# e-ink-display-v010.net
KiCad netlist of a schematic drawn in EAGLE
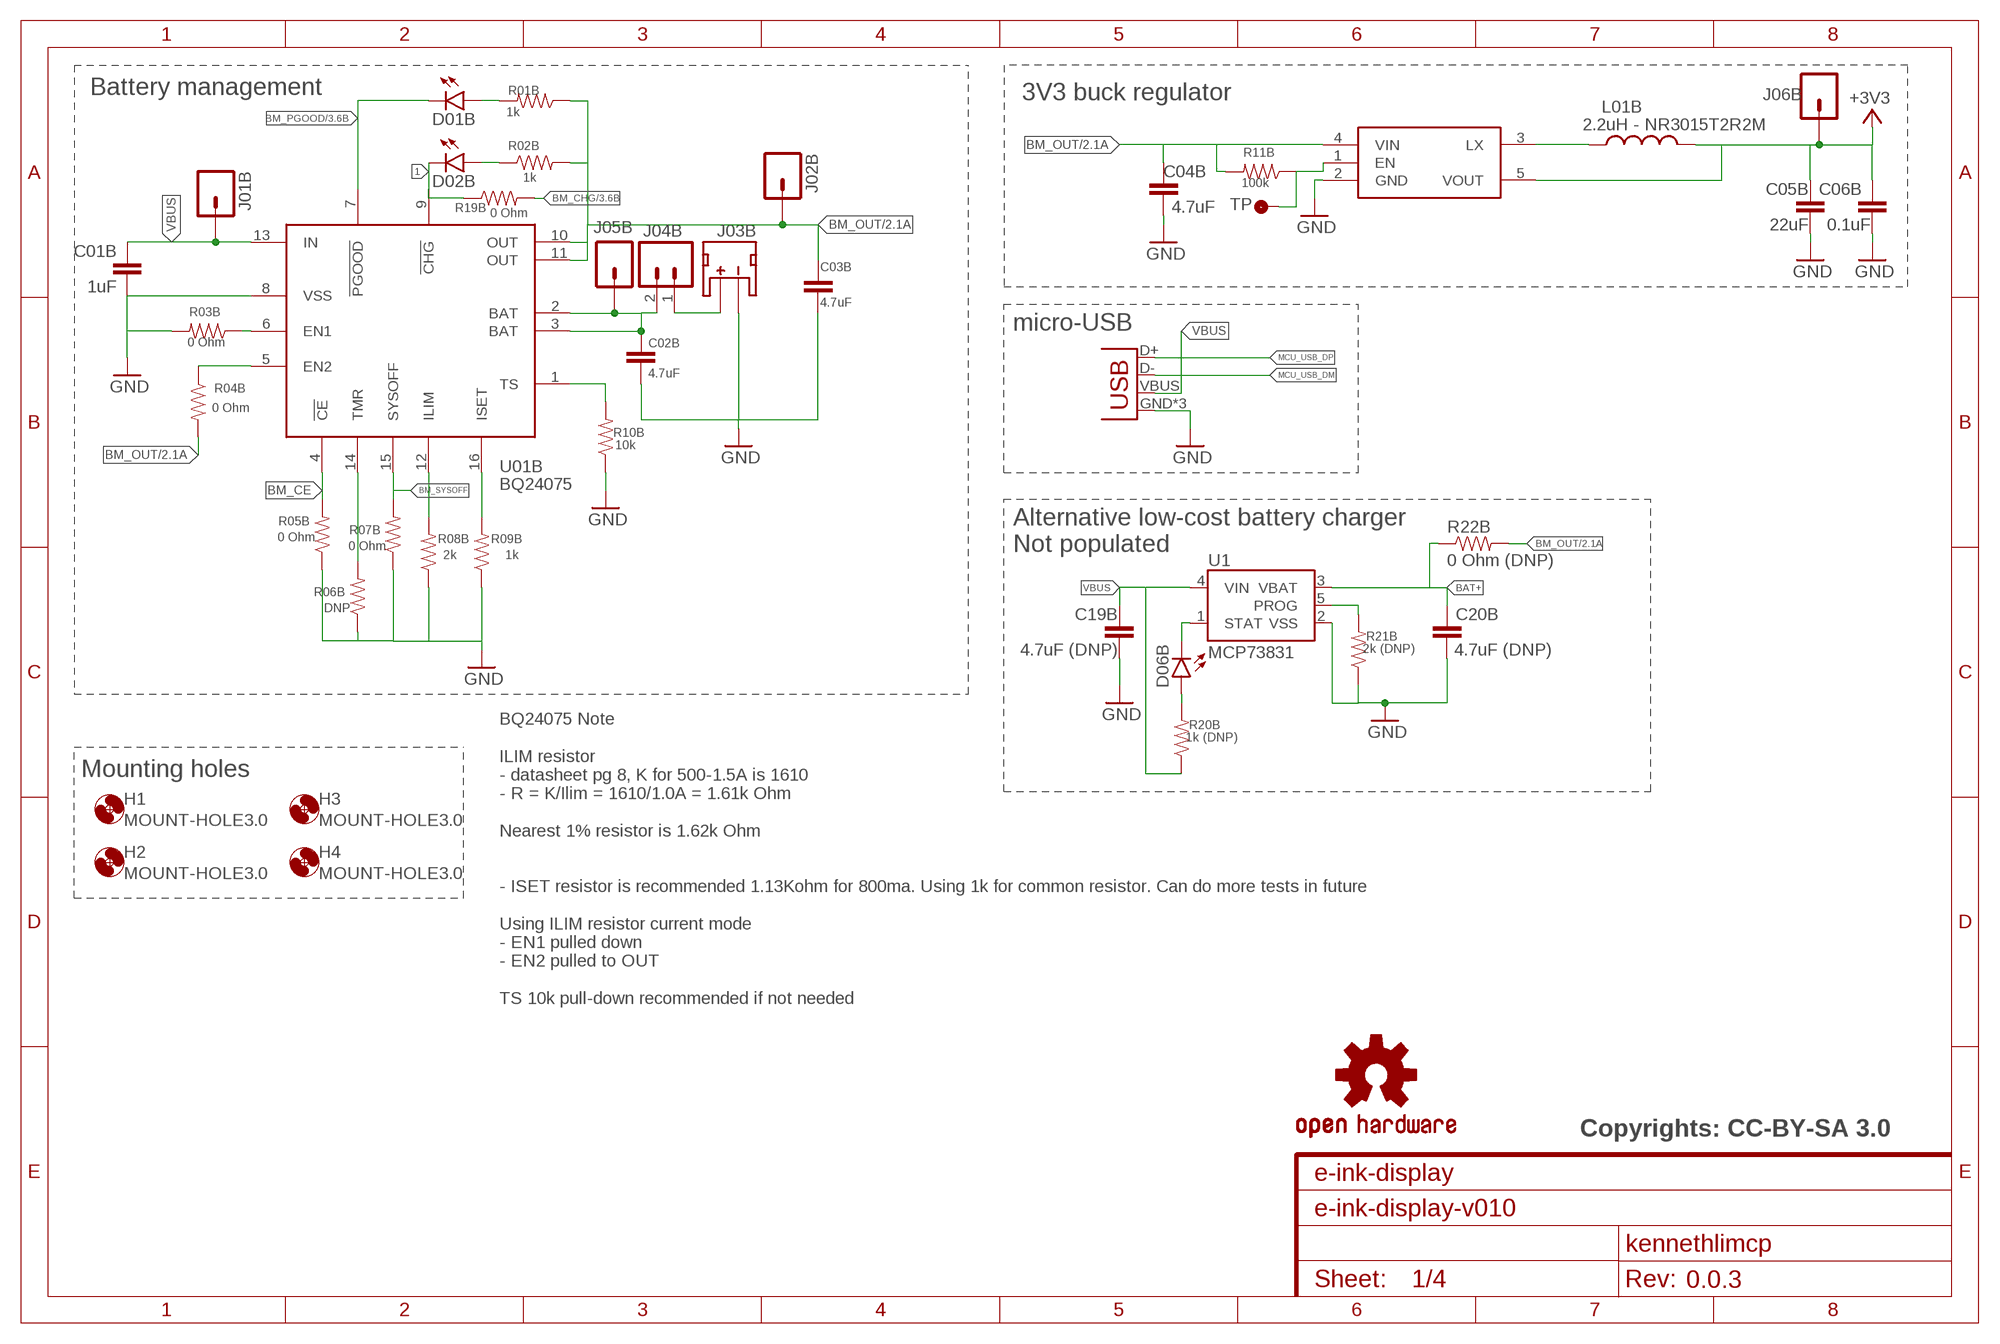
[diagram p0: schematic, sheet 1]
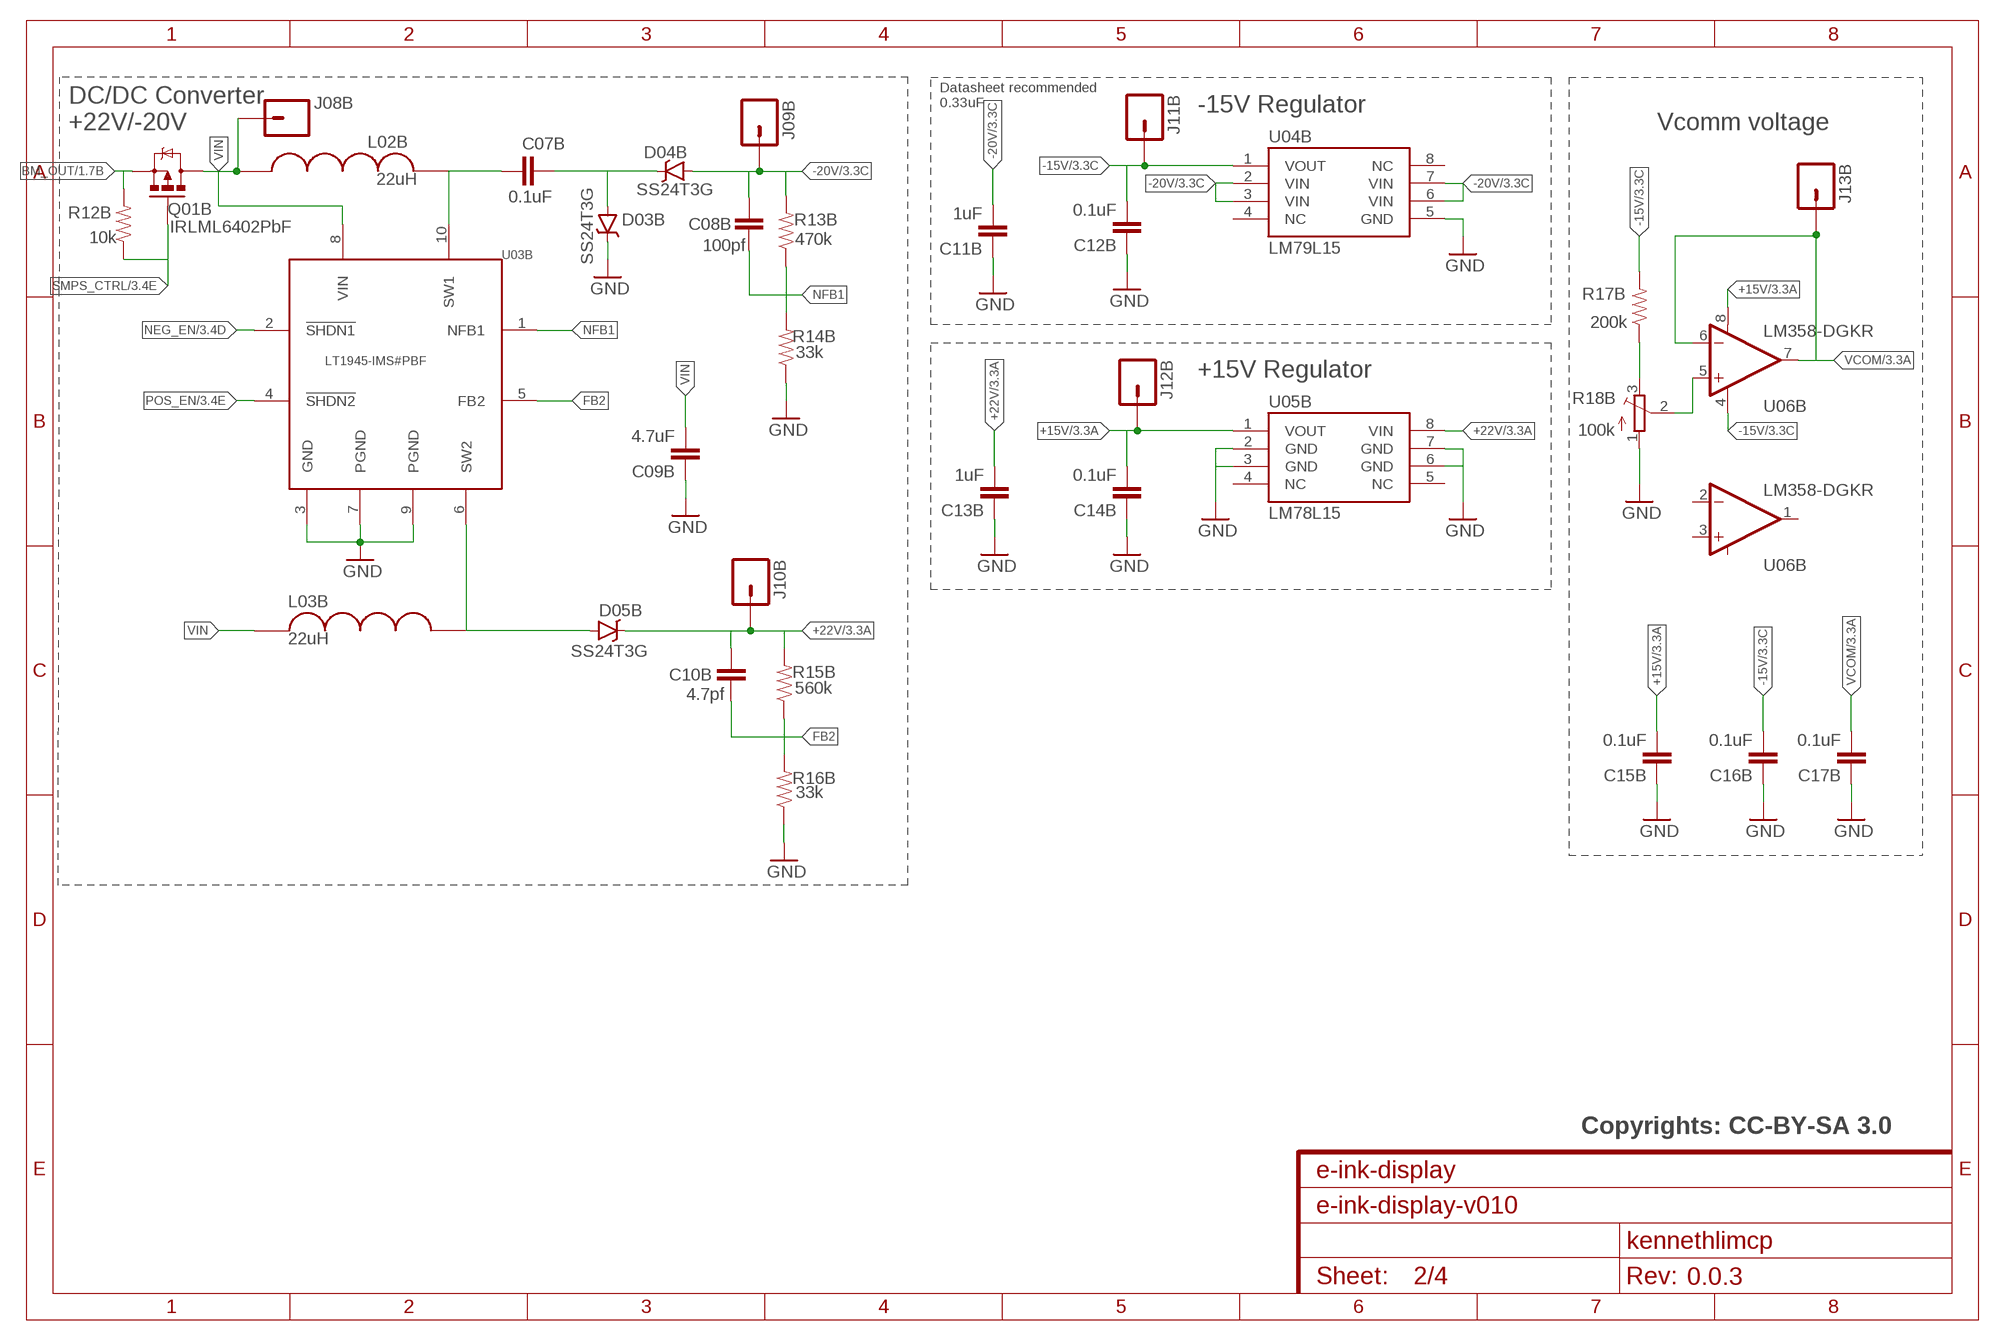
[diagram p1: schematic, sheet 2]
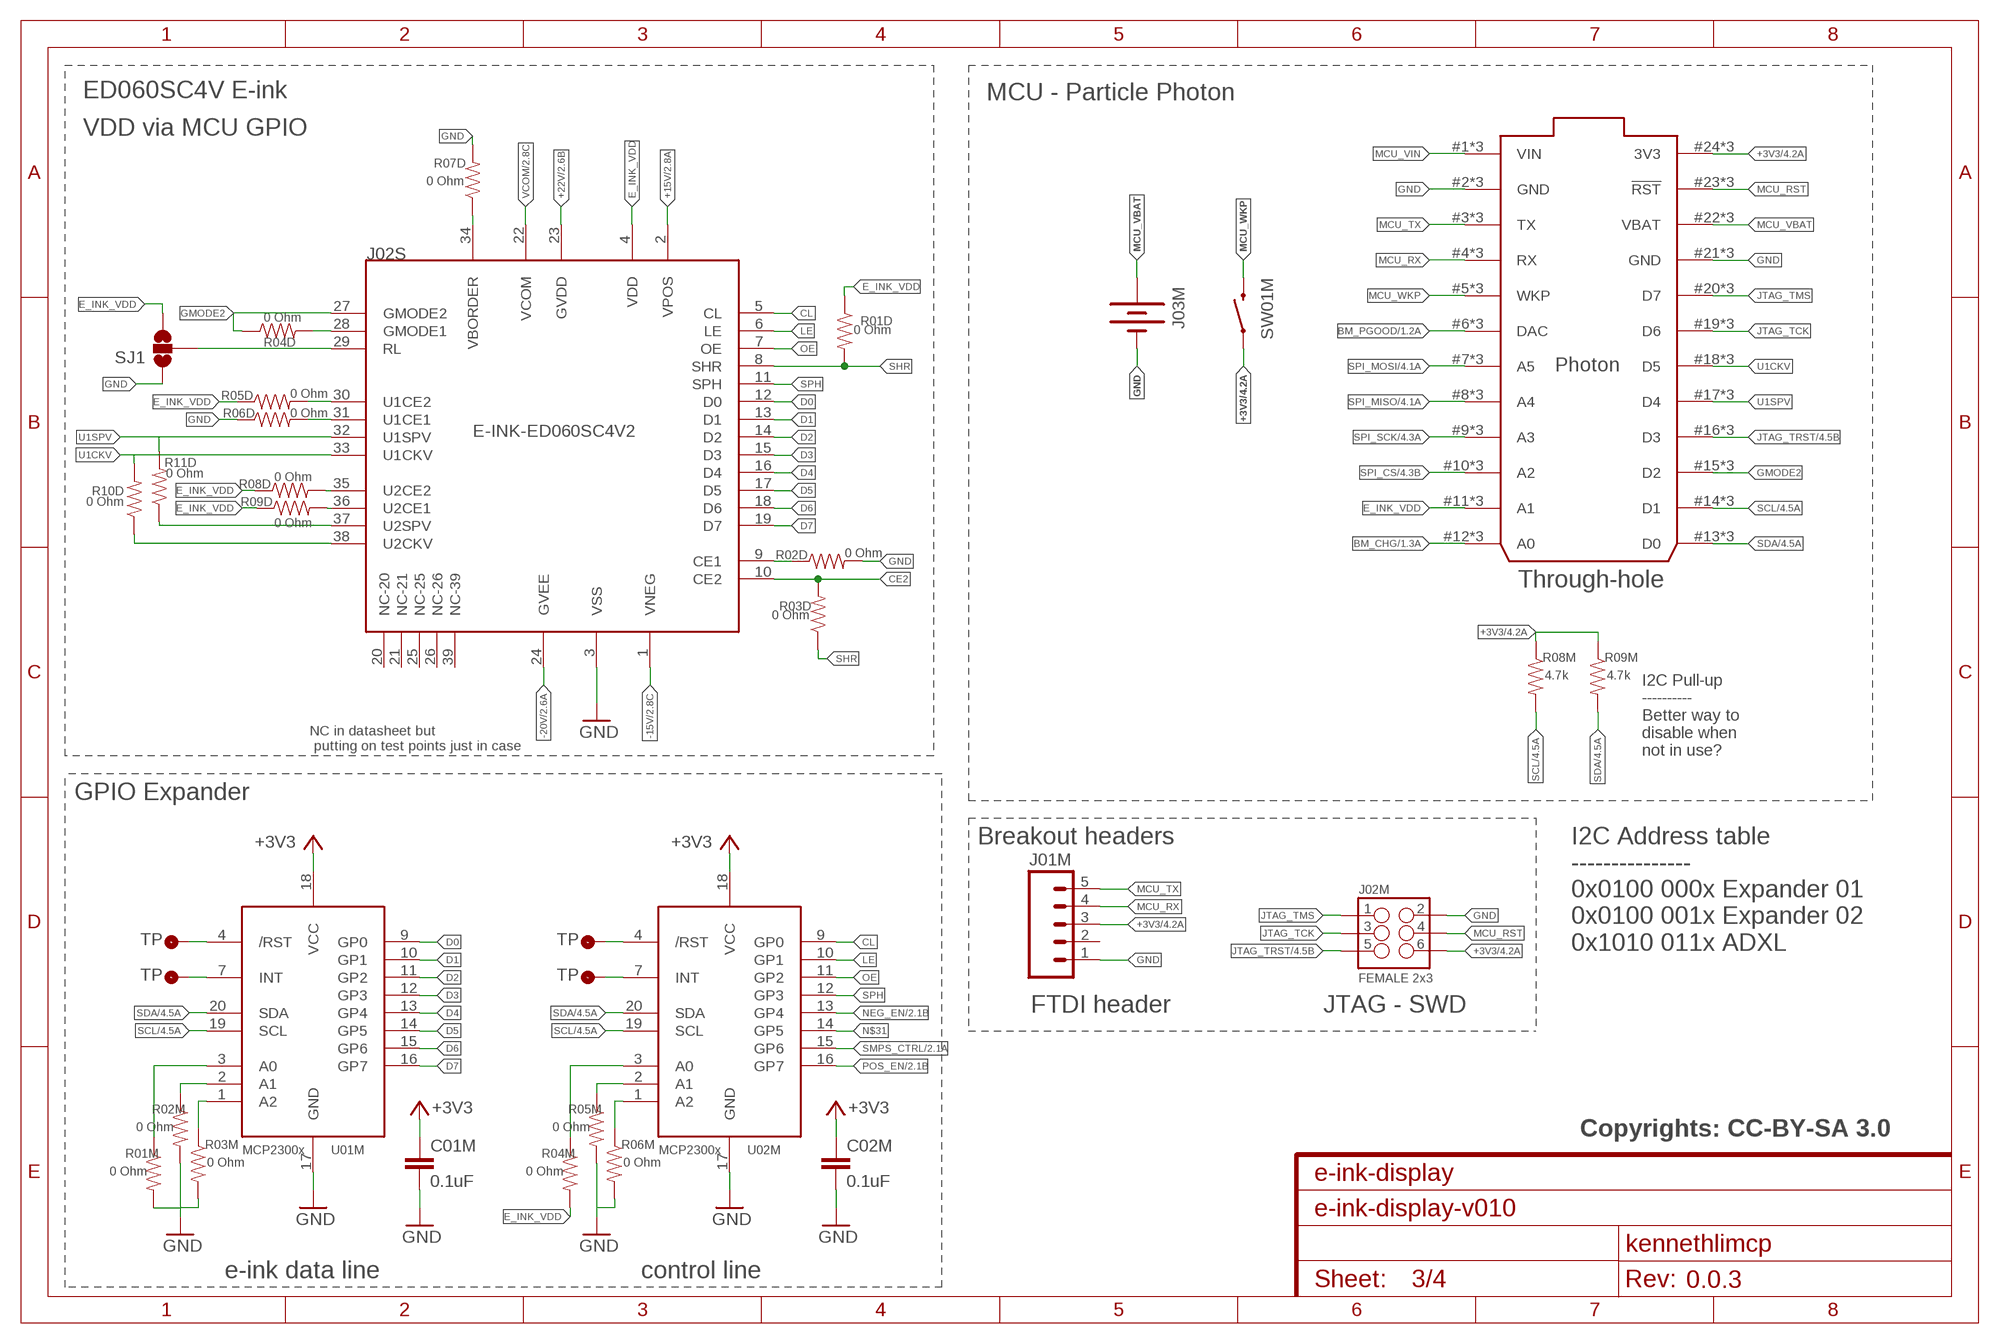
[diagram p2: schematic, sheet 3]
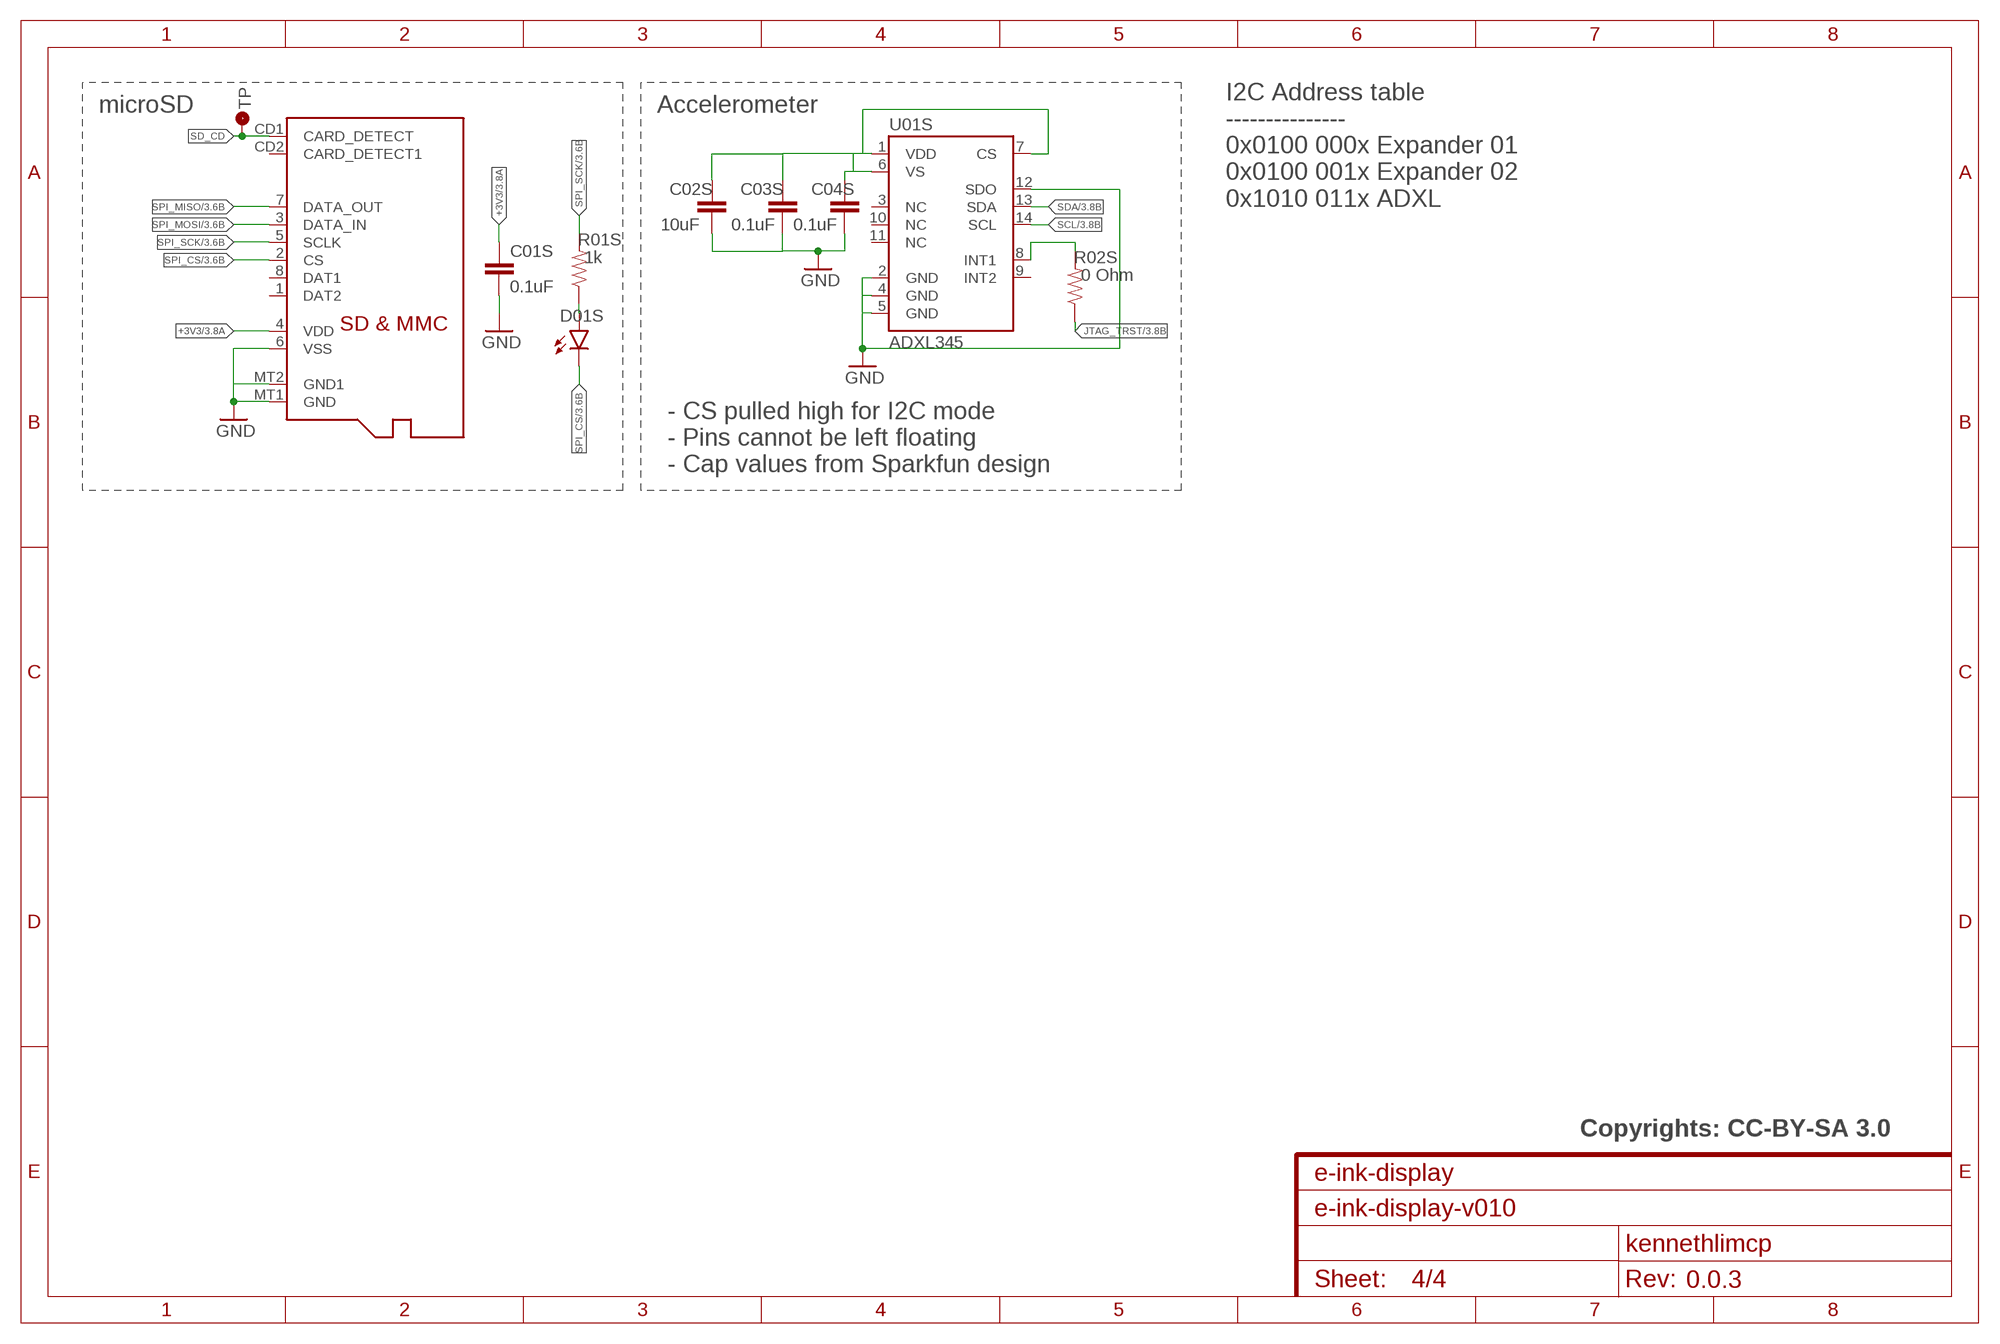
[diagram p3: schematic, sheet 4]

(export (version "E")
  (design (tool "Eeschema 10.0.6"))
  (components
    (comp (ref "C01S")
      (value "0.1uF")
      (footprint "eagle-import:0603-CAP")
      (libsource (lib "eagle-import") (part "CAP0603-CAP"))
    )
    (comp (ref "C02S")
      (value "10uF")
      (footprint "eagle-import:0603-CAP")
      (libsource (lib "eagle-import") (part "CAP0603-CAP"))
    )
    (comp (ref "C03S")
      (value "0.1uF")
      (footprint "eagle-import:0603-CAP")
      (libsource (lib "eagle-import") (part "CAP0603-CAP"))
    )
    (comp (ref "C04S")
      (value "0.1uF")
      (footprint "eagle-import:0603-CAP")
      (libsource (lib "eagle-import") (part "CAP0603-CAP"))
    )
    (comp (ref "D01S")
      (value "LED0603")
      (footprint "eagle-import:LED-0603")
      (libsource (lib "eagle-import") (part "LED0603"))
    )
    (comp (ref "J01S")
      (value "MICROSD")
      (footprint "eagle-import:MICROSD")
      (libsource (lib "eagle-import") (part "MICROSD"))
    )
    (comp (ref "R01S")
      (value "1k")
      (footprint "eagle-import:0603-RES")
      (libsource (lib "eagle-import") (part "SparkFun-Resistors_RESISTOR0603-RES"))
    )
    (comp (ref "R02S")
      (value "0 Ohm")
      (footprint "eagle-import:0603-RES")
      (libsource (lib "eagle-import") (part "RESISTOR0603"))
    )
    (comp (ref "U$5")
      (value "TP3")
      (footprint "eagle-import:TP60_BOT")
      (libsource (lib "eagle-import") (part "TP3"))
    )
    (comp (ref "U01S")
      (value "ADXL345")
      (footprint "eagle-import:LGA14")
      (libsource (lib "eagle-import") (part "ADXL345"))
    )
    (comp (ref "C01B")
      (value "1uF")
      (footprint "eagle-import:0603-CAP")
      (libsource (lib "eagle-import") (part "CAP0603-CAP"))
    )
    (comp (ref "C02B")
      (value "4.7uF")
      (footprint "eagle-import:0603-CAP")
      (libsource (lib "eagle-import") (part "CAP0603-CAP"))
    )
    (comp (ref "C03B")
      (value "4.7uF")
      (footprint "eagle-import:0603-CAP")
      (libsource (lib "eagle-import") (part "CAP0603-CAP"))
    )
    (comp (ref "C04B")
      (value "4.7uF")
      (footprint "eagle-import:0603-CAP")
      (libsource (lib "eagle-import") (part "CAP0603-CAP"))
    )
    (comp (ref "C05B")
      (value "22uF")
      (footprint "eagle-import:0603-CAP")
      (libsource (lib "eagle-import") (part "CAP0603-CAP"))
    )
    (comp (ref "C06B")
      (value "0.1uF")
      (footprint "eagle-import:0603-CAP")
      (libsource (lib "eagle-import") (part "CAP0603-CAP"))
    )
    (comp (ref "C19B")
      (value "4.7uF (DNP)")
      (footprint "eagle-import:0603-CAP")
      (libsource (lib "eagle-import") (part "CAP0603-CAP"))
    )
    (comp (ref "C20B")
      (value "4.7uF (DNP)")
      (footprint "eagle-import:0603-CAP")
      (libsource (lib "eagle-import") (part "CAP0603-CAP"))
    )
    (comp (ref "D01B")
      (value "LED0603")
      (footprint "eagle-import:LED-0603")
      (libsource (lib "eagle-import") (part "LED0603"))
    )
    (comp (ref "D02B")
      (value "LED0603")
      (footprint "eagle-import:LED-0603")
      (libsource (lib "eagle-import") (part "LED0603"))
    )
    (comp (ref "D06B")
      (value "LED0603")
      (footprint "eagle-import:LED-0603")
      (libsource (lib "eagle-import") (part "LED0603"))
    )
    (comp (ref "H1")
      (value "MOUNT-HOLE3.0")
      (footprint "eagle-import:3,0")
      (libsource (lib "eagle-import") (part "MOUNT-HOLE3.0"))
    )
    (comp (ref "H2")
      (value "MOUNT-HOLE3.0")
      (footprint "eagle-import:3,0")
      (libsource (lib "eagle-import") (part "MOUNT-HOLE3.0"))
    )
    (comp (ref "H3")
      (value "MOUNT-HOLE3.0")
      (footprint "eagle-import:3,0")
      (libsource (lib "eagle-import") (part "MOUNT-HOLE3.0"))
    )
    (comp (ref "H4")
      (value "MOUNT-HOLE3.0")
      (footprint "eagle-import:3,0")
      (libsource (lib "eagle-import") (part "MOUNT-HOLE3.0"))
    )
    (comp (ref "J01B")
      (value "M01PTH")
      (footprint "eagle-import:1X01")
      (libsource (lib "eagle-import") (part "M01PTH"))
    )
    (comp (ref "J02B")
      (value "M01PTH")
      (footprint "eagle-import:1X01")
      (libsource (lib "eagle-import") (part "M01PTH"))
    )
    (comp (ref "J03B")
      (value "JST_2MM_MALE")
      (footprint "eagle-import:JST-2-SMD")
      (libsource (lib "eagle-import") (part "JST_2MM_MALE"))
    )
    (comp (ref "J04B")
      (value "M02PTH")
      (footprint "eagle-import:1X02")
      (libsource (lib "eagle-import") (part "M02PTH"))
    )
    (comp (ref "J05B")
      (value "M01PTH")
      (footprint "eagle-import:1X01")
      (libsource (lib "eagle-import") (part "M01PTH"))
    )
    (comp (ref "J06B")
      (value "M01PTH")
      (footprint "eagle-import:1X01")
      (libsource (lib "eagle-import") (part "M01PTH"))
    )
    (comp (ref "J07B")
      (value "USBUSB-MICROB-SLOT-HOLE")
      (footprint "eagle-import:USB-MICROB-SLOT-HOLE")
      (libsource (lib "eagle-import") (part "USBUSB-MICROB-SLOT-HOLE"))
    )
    (comp (ref "L01B")
      (value "2.2uH - NR3015T2R2M")
      (footprint "eagle-import:INDUCTOR-NR3015")
      (libsource (lib "eagle-import") (part "INDUCTOR-SPARKFUNNR3015T4R7M"))
    )
    (comp (ref "LOGO1")
      (value "OSHW-LOGOPAD")
      (footprint "eagle-import:OSHW-LOGO-M-PAD")
      (libsource (lib "eagle-import") (part "OSHW-LOGOPAD"))
    )
    (comp (ref "R01B")
      (value "1k")
      (footprint "eagle-import:0603-RES")
      (libsource (lib "eagle-import") (part "SparkFun-Resistors_RESISTOR0603-RES"))
    )
    (comp (ref "R02B")
      (value "1k")
      (footprint "eagle-import:0603-RES")
      (libsource (lib "eagle-import") (part "SparkFun-Resistors_RESISTOR0603-RES"))
    )
    (comp (ref "R03B")
      (value "0 Ohm")
      (footprint "eagle-import:0603-RES")
      (libsource (lib "eagle-import") (part "SparkFun-Resistors_RESISTOR0603-RES"))
    )
    (comp (ref "R04B")
      (value "0 Ohm")
      (footprint "eagle-import:0603-RES")
      (libsource (lib "eagle-import") (part "RESISTOR0603"))
    )
    (comp (ref "R05B")
      (value "0 Ohm")
      (footprint "eagle-import:0603-RES")
      (libsource (lib "eagle-import") (part "RESISTOR0603"))
    )
    (comp (ref "R06B")
      (value "DNP")
      (footprint "eagle-import:0603-RES")
      (libsource (lib "eagle-import") (part "RESISTOR0603"))
    )
    (comp (ref "R07B")
      (value "0 Ohm")
      (footprint "eagle-import:0603-RES")
      (libsource (lib "eagle-import") (part "RESISTOR0603"))
    )
    (comp (ref "R08B")
      (value "2k")
      (footprint "eagle-import:0603-RES")
      (libsource (lib "eagle-import") (part "RESISTOR0603"))
    )
    (comp (ref "R09B")
      (value "1k")
      (footprint "eagle-import:0603-RES")
      (libsource (lib "eagle-import") (part "SparkFun-Resistors_RESISTOR0603-RES"))
    )
    (comp (ref "R10B")
      (value "10k")
      (footprint "eagle-import:0603-RES")
      (libsource (lib "eagle-import") (part "RESISTOR0603"))
    )
    (comp (ref "R11B")
      (value "100k")
      (footprint "eagle-import:0603-RES")
      (libsource (lib "eagle-import") (part "RESISTOR0603"))
    )
    (comp (ref "R19B")
      (value "0 Ohm")
      (footprint "eagle-import:0603-RES")
      (libsource (lib "eagle-import") (part "RESISTOR0603"))
    )
    (comp (ref "R20B")
      (value "1k (DNP)")
      (footprint "eagle-import:0603-RES")
      (libsource (lib "eagle-import") (part "RESISTOR0603"))
    )
    (comp (ref "R21B")
      (value "2k (DNP)")
      (footprint "eagle-import:0603-RES")
      (libsource (lib "eagle-import") (part "RESISTOR0603"))
    )
    (comp (ref "R22B")
      (value "0 Ohm (DNP)")
      (footprint "eagle-import:1206")
      (libsource (lib "eagle-import") (part "SparkFun-Resistors_RESISTOR1206"))
    )
    (comp (ref "TP01B")
      (value "TP1")
      (footprint "eagle-import:TP35_BOT")
      (libsource (lib "eagle-import") (part "TP1"))
    )
    (comp (ref "U1")
      (value "MCP73831")
      (footprint "eagle-import:SOT23-5")
      (libsource (lib "eagle-import") (part "MCP73831"))
    )
    (comp (ref "U01B")
      (value "BQ24075")
      (footprint "eagle-import:PVQFN-16")
      (libsource (lib "eagle-import") (part "BQ2407"))
    )
    (comp (ref "U02B")
      (value "R8008-33")
      (footprint "eagle-import:SOT23-5")
      (libsource (lib "eagle-import") (part "R8008-33"))
    )
    (comp (ref "C07B")
      (value "0.1uF")
      (footprint "eagle-import:0603-CAP")
      (libsource (lib "eagle-import") (part "CAP0603-CAP"))
    )
    (comp (ref "C08B")
      (value "100pf")
      (footprint "eagle-import:0603-CAP")
      (libsource (lib "eagle-import") (part "CAP0603-CAP"))
    )
    (comp (ref "C09B")
      (value "4.7uF")
      (footprint "eagle-import:0603-CAP")
      (libsource (lib "eagle-import") (part "CAP0603-CAP"))
    )
    (comp (ref "C10B")
      (value "4.7pf")
      (footprint "eagle-import:0603-CAP")
      (libsource (lib "eagle-import") (part "CAP0603-CAP"))
    )
    (comp (ref "C11B")
      (value "1uF")
      (footprint "eagle-import:0603-CAP")
      (libsource (lib "eagle-import") (part "CAP0603-CAP"))
    )
    (comp (ref "C12B")
      (value "0.1uF")
      (footprint "eagle-import:0603-CAP")
      (libsource (lib "eagle-import") (part "CAP0603-CAP"))
    )
    (comp (ref "C13B")
      (value "1uF")
      (footprint "eagle-import:0603-CAP")
      (libsource (lib "eagle-import") (part "CAP0603-CAP"))
    )
    (comp (ref "C14B")
      (value "0.1uF")
      (footprint "eagle-import:0603-CAP")
      (libsource (lib "eagle-import") (part "CAP0603-CAP"))
    )
    (comp (ref "C15B")
      (value "0.1uF")
      (footprint "eagle-import:0603-CAP")
      (libsource (lib "eagle-import") (part "CAP0603-CAP"))
    )
    (comp (ref "C16B")
      (value "0.1uF")
      (footprint "eagle-import:0603-CAP")
      (libsource (lib "eagle-import") (part "CAP0603-CAP"))
    )
    (comp (ref "C17B")
      (value "0.1uF")
      (footprint "eagle-import:0603-CAP")
      (libsource (lib "eagle-import") (part "CAP0603-CAP"))
    )
    (comp (ref "D03B")
      (value "SS24T3G")
      (footprint "eagle-import:SMA-DIODE")
      (libsource (lib "eagle-import") (part "SS24T3G"))
    )
    (comp (ref "D04B")
      (value "SS24T3G")
      (footprint "eagle-import:SMA-DIODE")
      (libsource (lib "eagle-import") (part "SS24T3G"))
    )
    (comp (ref "D05B")
      (value "SS24T3G")
      (footprint "eagle-import:SMA-DIODE")
      (libsource (lib "eagle-import") (part "SS24T3G"))
    )
    (comp (ref "J08B")
      (value "M01PTH")
      (footprint "eagle-import:1X01")
      (libsource (lib "eagle-import") (part "M01PTH"))
    )
    (comp (ref "J09B")
      (value "M01PTH")
      (footprint "eagle-import:1X01")
      (libsource (lib "eagle-import") (part "M01PTH"))
    )
    (comp (ref "J10B")
      (value "M01PTH")
      (footprint "eagle-import:1X01")
      (libsource (lib "eagle-import") (part "M01PTH"))
    )
    (comp (ref "J11B")
      (value "M01PTH")
      (footprint "eagle-import:1X01")
      (libsource (lib "eagle-import") (part "M01PTH"))
    )
    (comp (ref "J12B")
      (value "M01PTH")
      (footprint "eagle-import:1X01")
      (libsource (lib "eagle-import") (part "M01PTH"))
    )
    (comp (ref "J13B")
      (value "M01PTH")
      (footprint "eagle-import:1X01")
      (libsource (lib "eagle-import") (part "M01PTH"))
    )
    (comp (ref "L02B")
      (value "22uH")
      (footprint "eagle-import:4040(1515)")
      (libsource (lib "eagle-import") (part "INDUCTOR"))
    )
    (comp (ref "L03B")
      (value "22uH")
      (footprint "eagle-import:4040(1515)")
      (libsource (lib "eagle-import") (part "INDUCTOR"))
    )
    (comp (ref "Q01B")
      (value "IRLML6402PbF")
      (footprint "eagle-import:SOT23-3")
      (libsource (lib "eagle-import") (part "MOSFET-PCHANNELSMD"))
    )
    (comp (ref "R12B")
      (value "10k")
      (footprint "eagle-import:0603-RES")
      (libsource (lib "eagle-import") (part "RESISTOR0603"))
    )
    (comp (ref "R13B")
      (value "470k")
      (footprint "eagle-import:0603-RES")
      (libsource (lib "eagle-import") (part "RESISTOR0603"))
    )
    (comp (ref "R14B")
      (value "33k")
      (footprint "eagle-import:0603-RES")
      (libsource (lib "eagle-import") (part "RESISTOR0603"))
    )
    (comp (ref "R15B")
      (value "560k")
      (footprint "eagle-import:0603-RES")
      (libsource (lib "eagle-import") (part "RESISTOR0603"))
    )
    (comp (ref "R16B")
      (value "33k")
      (footprint "eagle-import:0603-RES")
      (libsource (lib "eagle-import") (part "RESISTOR0603"))
    )
    (comp (ref "R17B")
      (value "200k")
      (footprint "eagle-import:0603-RES")
      (libsource (lib "eagle-import") (part "RESISTOR0603"))
    )
    (comp (ref "R18B")
      (value "100k")
      (footprint "eagle-import:TC33X")
      (libsource (lib "eagle-import") (part "TRIMPOTTC33X"))
    )
    (comp (ref "U03B")
      (value "LT1945-IMS#PBF")
      (footprint "eagle-import:MSOP-10")
      (libsource (lib "eagle-import") (part "LT1945-IMS#PBF"))
    )
    (comp (ref "U04B")
      (value "LM79L15")
      (footprint "eagle-import:SO08")
      (libsource (lib "eagle-import") (part "LM79L15"))
    )
    (comp (ref "U05B")
      (value "LM78L15")
      (footprint "eagle-import:SO08")
      (libsource (lib "eagle-import") (part "LM78L15"))
    )
    (comp (ref "U06B")
      (value "LM358-DGKR")
      (footprint "eagle-import:MSOP-8")
      (libsource (lib "eagle-import") (part "LM358-DGKR"))
    )
    (comp (ref "C01M")
      (value "0.1uF")
      (footprint "eagle-import:0603-CAP")
      (libsource (lib "eagle-import") (part "CAP0603-CAP"))
    )
    (comp (ref "C02M")
      (value "0.1uF")
      (footprint "eagle-import:0603-CAP")
      (libsource (lib "eagle-import") (part "CAP0603-CAP"))
    )
    (comp (ref "J01M")
      (value "M05PTH")
      (footprint "eagle-import:1X05")
      (libsource (lib "eagle-import") (part "M05PTH"))
    )
    (comp (ref "J02M")
      (value "FEMALE 2x3")
      (footprint "eagle-import:2X3")
      (libsource (lib "eagle-import") (part "M03X2FEMALE"))
    )
    (comp (ref "J02S")
      (value "E-INK-ED060SC4V2")
      (footprint "eagle-import:FPC-0.3-39")
      (libsource (lib "eagle-import") (part "E-INK-ED060SC4V2"))
    )
    (comp (ref "J03M")
      (value "BATTERY20PTH")
      (footprint "eagle-import:BATTCOM_20MM_PTH")
      (libsource (lib "eagle-import") (part "BATTERY20PTH"))
    )
    (comp (ref "R01D")
      (value "0 Ohm")
      (footprint "eagle-import:0603-RES")
      (libsource (lib "eagle-import") (part "RESISTOR0603-RES"))
    )
    (comp (ref "R01M")
      (value "0 Ohm")
      (footprint "eagle-import:0603-RES")
      (libsource (lib "eagle-import") (part "RESISTOR0603-RES"))
    )
    (comp (ref "R02D")
      (value "0 Ohm")
      (footprint "eagle-import:0603-RES")
      (libsource (lib "eagle-import") (part "RESISTOR0603-RES"))
    )
    (comp (ref "R02M")
      (value "0 Ohm")
      (footprint "eagle-import:0603-RES")
      (libsource (lib "eagle-import") (part "RESISTOR0603-RES"))
    )
    (comp (ref "R03D")
      (value "0 Ohm")
      (footprint "eagle-import:0603-RES")
      (libsource (lib "eagle-import") (part "RESISTOR0603-RES"))
    )
    (comp (ref "R03M")
      (value "0 Ohm")
      (footprint "eagle-import:0603-RES")
      (libsource (lib "eagle-import") (part "RESISTOR0603-RES"))
    )
    (comp (ref "R04D")
      (value "0 Ohm")
      (footprint "eagle-import:0603-RES")
      (libsource (lib "eagle-import") (part "RESISTOR0603-RES"))
    )
    (comp (ref "R04M")
      (value "0 Ohm")
      (footprint "eagle-import:0603-RES")
      (libsource (lib "eagle-import") (part "RESISTOR0603-RES"))
    )
    (comp (ref "R05D")
      (value "0 Ohm")
      (footprint "eagle-import:0603-RES")
      (libsource (lib "eagle-import") (part "RESISTOR0603-RES"))
    )
    (comp (ref "R05M")
      (value "0 Ohm")
      (footprint "eagle-import:0603-RES")
      (libsource (lib "eagle-import") (part "RESISTOR0603-RES"))
    )
    (comp (ref "R06D")
      (value "0 Ohm")
      (footprint "eagle-import:0603-RES")
      (libsource (lib "eagle-import") (part "RESISTOR0603-RES"))
    )
    (comp (ref "R06M")
      (value "0 Ohm")
      (footprint "eagle-import:0603-RES")
      (libsource (lib "eagle-import") (part "RESISTOR0603-RES"))
    )
    (comp (ref "R07D")
      (value "0 Ohm")
      (footprint "eagle-import:0603-RES")
      (libsource (lib "eagle-import") (part "RESISTOR0603-RES"))
    )
    (comp (ref "R08D")
      (value "0 Ohm")
      (footprint "eagle-import:0603-RES")
      (libsource (lib "eagle-import") (part "RESISTOR0603-RES"))
    )
    (comp (ref "R08M")
      (value "4.7k")
      (footprint "eagle-import:0603-RES")
      (libsource (lib "eagle-import") (part "RESISTOR0603-RES"))
    )
    (comp (ref "R09D")
      (value "0 Ohm")
      (footprint "eagle-import:0603-RES")
      (libsource (lib "eagle-import") (part "RESISTOR0603-RES"))
    )
    (comp (ref "R09M")
      (value "4.7k")
      (footprint "eagle-import:0603-RES")
      (libsource (lib "eagle-import") (part "RESISTOR0603-RES"))
    )
    (comp (ref "R10D")
      (value "0 Ohm")
      (footprint "eagle-import:0603-RES")
      (libsource (lib "eagle-import") (part "RESISTOR0603-RES"))
    )
    (comp (ref "R11D")
      (value "0 Ohm")
      (footprint "eagle-import:0603-RES")
      (libsource (lib "eagle-import") (part "RESISTOR0603-RES"))
    )
    (comp (ref "SJ1")
      (value "SOLDERJUMPER_2WAYT")
      (footprint "eagle-import:SJ_2")
      (libsource (lib "eagle-import") (part "SOLDERJUMPER_2WAYT"))
    )
    (comp (ref "SW01M")
      (value "SWITCH-MOMENTARY-2PTH")
      (footprint "eagle-import:TACTILE-PTH")
      (libsource (lib "eagle-import") (part "SWITCH-MOMENTARY-2PTH"))
    )
    (comp (ref "U$1")
      (value "TP1")
      (footprint "eagle-import:TP35_BOT")
      (libsource (lib "eagle-import") (part "TP1"))
    )
    (comp (ref "U$2")
      (value "TP1")
      (footprint "eagle-import:TP35_BOT")
      (libsource (lib "eagle-import") (part "TP1"))
    )
    (comp (ref "U$3")
      (value "TP1")
      (footprint "eagle-import:TP35_BOT")
      (libsource (lib "eagle-import") (part "TP1"))
    )
    (comp (ref "U$4")
      (value "TP1")
      (footprint "eagle-import:TP35_BOT")
      (libsource (lib "eagle-import") (part "TP1"))
    )
    (comp (ref "U01M")
      (value "MCP2300X/QFN")
      (footprint "eagle-import:QFN-20(4X4)")
      (libsource (lib "eagle-import") (part "MCP2300X/QFN"))
    )
    (comp (ref "U02M")
      (value "MCP2300X/QFN")
      (footprint "eagle-import:QFN-20(4X4)")
      (libsource (lib "eagle-import") (part "MCP2300X/QFN"))
    )
    (comp (ref "U03M")
      (value "PHOTON_WITH_STACKABLE_HEADERS")
      (footprint "eagle-import:PHOTON_STACKABLE")
      (libsource (lib "eagle-import") (part "PHOTON_WITH_STACKABLE_HEADERS"))
    )
  )
  (nets
    (net (code "1") (name "+3V3") (class "Default")
      (node (ref "C01M") (pin "1") (pinfunction "1_1") (pintype "passive"))
      (node (ref "C01S") (pin "1") (pinfunction "1_1") (pintype "passive"))
      (node (ref "C02M") (pin "1") (pinfunction "1_1") (pintype "passive"))
      (node (ref "C05B") (pin "2") (pinfunction "2_2") (pintype "passive"))
      (node (ref "C06B") (pin "2") (pinfunction "2_2") (pintype "passive"))
      (node (ref "J01M") (pin "3") (pinfunction "3_3") (pintype "passive"))
      (node (ref "J01S") (pin "4") (pinfunction "VDD_4") (pintype "power_in"))
      (node (ref "J02M") (pin "6") (pinfunction "6_6") (pintype "bidirectional"))
      (node (ref "J06B") (pin "1") (pinfunction "1_1") (pintype "passive"))
      (node (ref "L01B") (pin "2") (pinfunction "2_2") (pintype "passive"))
      (node (ref "R08M") (pin "1") (pinfunction "1_1") (pintype "passive"))
      (node (ref "R09M") (pin "1") (pinfunction "1_1") (pintype "passive"))
      (node (ref "SW01M") (pin "1") (pinfunction "1_1") (pintype "passive"))
      (node (ref "U01M") (pin "18") (pinfunction "VCC_18") (pintype "power_in"))
      (node (ref "U02B") (pin "5") (pinfunction "VOUT_5") (pintype "bidirectional"))
      (node (ref "U02M") (pin "18") (pinfunction "VCC_18") (pintype "power_in"))
      (node (ref "U03M") (pin "#24") (pinfunction "3V3_#24") (pintype "power_in"))
      (node (ref "U03M") (pin "24") (pinfunction "3V3_24") (pintype "power_in"))
      (node (ref "U03M") (pin "@24") (pinfunction "3V3_@24") (pintype "power_in"))
    )
    (net (code "2") (name "+15V") (class "Default")
      (node (ref "C14B") (pin "2") (pinfunction "2_2") (pintype "passive"))
      (node (ref "C15B") (pin "2") (pinfunction "2_2") (pintype "passive"))
      (node (ref "J02S") (pin "2") (pinfunction "VPOS_2") (pintype "bidirectional"))
      (node (ref "J12B") (pin "1") (pinfunction "1_1") (pintype "passive"))
      (node (ref "U05B") (pin "1") (pinfunction "VOUT_1") (pintype "bidirectional"))
      (node (ref "U06B") (pin "8") (pinfunction "V+_8") (pintype "power_in"))
    )
    (net (code "3") (name "+22V") (class "Default")
      (node (ref "C10B") (pin "2") (pinfunction "2_2") (pintype "passive"))
      (node (ref "C13B") (pin "2") (pinfunction "2_2") (pintype "passive"))
      (node (ref "D05B") (pin "C") (pinfunction "C_C") (pintype "passive"))
      (node (ref "J02S") (pin "23") (pinfunction "GVDD_23") (pintype "bidirectional"))
      (node (ref "J10B") (pin "1") (pinfunction "1_1") (pintype "passive"))
      (node (ref "R15B") (pin "2") (pinfunction "2_2") (pintype "passive"))
      (node (ref "U05B") (pin "8") (pinfunction "VIN_8") (pintype "bidirectional"))
    )
    (net (code "4") (name "-15V") (class "Default")
      (node (ref "C12B") (pin "2") (pinfunction "2_2") (pintype "passive"))
      (node (ref "C16B") (pin "2") (pinfunction "2_2") (pintype "passive"))
      (node (ref "J02S") (pin "1") (pinfunction "VNEG_1") (pintype "bidirectional"))
      (node (ref "J11B") (pin "1") (pinfunction "1_1") (pintype "passive"))
      (node (ref "R17B") (pin "2") (pinfunction "2_2") (pintype "passive"))
      (node (ref "U04B") (pin "1") (pinfunction "VOUT_1") (pintype "bidirectional"))
      (node (ref "U06B") (pin "4") (pinfunction "V-_4") (pintype "power_in"))
    )
    (net (code "5") (name "-20V") (class "Default")
      (node (ref "C08B") (pin "2") (pinfunction "2_2") (pintype "passive"))
      (node (ref "C11B") (pin "2") (pinfunction "2_2") (pintype "passive"))
      (node (ref "D04B") (pin "A") (pinfunction "A_A") (pintype "passive"))
      (node (ref "J02S") (pin "24") (pinfunction "GVEE_24") (pintype "bidirectional"))
      (node (ref "J09B") (pin "1") (pinfunction "1_1") (pintype "passive"))
      (node (ref "R13B") (pin "2") (pinfunction "2_2") (pintype "passive"))
      (node (ref "U04B") (pin "2") (pinfunction "VIN_2") (pintype "bidirectional"))
      (node (ref "U04B") (pin "3") (pinfunction "VIN_3") (pintype "bidirectional"))
      (node (ref "U04B") (pin "6") (pinfunction "VIN_6") (pintype "bidirectional"))
      (node (ref "U04B") (pin "7") (pinfunction "VIN_7") (pintype "bidirectional"))
    )
    (net (code "6") (name "1") (class "Default")
      (node (ref "D02B") (pin "C") (pinfunction "C_C") (pintype "passive"))
      (node (ref "R19B") (pin "1") (pinfunction "1_1") (pintype "passive"))
      (node (ref "U01B") (pin "9") (pinfunction "~{CHG}_9") (pintype "bidirectional"))
    )
    (net (code "7") (name "BAT+") (class "Default")
      (node (ref "C20B") (pin "2") (pinfunction "2_2") (pintype "passive"))
      (node (ref "J03B") (pin "2") (pinfunction "+_2") (pintype "bidirectional"))
      (node (ref "J04B") (pin "1") (pinfunction "1_1") (pintype "passive"))
      (node (ref "R22B") (pin "1") (pinfunction "1_1") (pintype "passive"))
      (node (ref "U1") (pin "3") (pinfunction "VBAT_3") (pintype "power_in"))
    )
    (net (code "8") (name "BM_CE") (class "Default")
      (node (ref "R05B") (pin "2") (pinfunction "2_2") (pintype "passive"))
      (node (ref "U01B") (pin "4") (pinfunction "~{CE}_4") (pintype "bidirectional"))
    )
    (net (code "9") (name "BM_CHG") (class "Default")
      (node (ref "R19B") (pin "2") (pinfunction "2_2") (pintype "passive"))
      (node (ref "U03M") (pin "#12") (pinfunction "A0_#12") (pintype "bidirectional"))
      (node (ref "U03M") (pin "12") (pinfunction "A0_12") (pintype "bidirectional"))
      (node (ref "U03M") (pin "@12") (pinfunction "A0_@12") (pintype "bidirectional"))
    )
    (net (code "10") (name "BM_OUT") (class "Default")
      (node (ref "C03B") (pin "2") (pinfunction "2_2") (pintype "passive"))
      (node (ref "C04B") (pin "2") (pinfunction "2_2") (pintype "passive"))
      (node (ref "J02B") (pin "1") (pinfunction "1_1") (pintype "passive"))
      (node (ref "Q01B") (pin "2") (pinfunction "S_2") (pintype "passive"))
      (node (ref "R01B") (pin "1") (pinfunction "1_1") (pintype "passive"))
      (node (ref "R02B") (pin "2") (pinfunction "2_2") (pintype "passive"))
      (node (ref "R04B") (pin "2") (pinfunction "2_2") (pintype "passive"))
      (node (ref "R11B") (pin "2") (pinfunction "2_2") (pintype "passive"))
      (node (ref "R12B") (pin "2") (pinfunction "2_2") (pintype "passive"))
      (node (ref "R22B") (pin "2") (pinfunction "2_2") (pintype "passive"))
      (node (ref "U01B") (pin "10") (pinfunction "OUT_10") (pintype "bidirectional"))
      (node (ref "U01B") (pin "11") (pinfunction "OUT_11") (pintype "bidirectional"))
      (node (ref "U02B") (pin "4") (pinfunction "VIN_4") (pintype "bidirectional"))
    )
    (net (code "11") (name "BM_PGOOD") (class "Default")
      (node (ref "D01B") (pin "C") (pinfunction "C_C") (pintype "passive"))
      (node (ref "U01B") (pin "7") (pinfunction "~{PGOOD}_7") (pintype "bidirectional"))
      (node (ref "U03M") (pin "#6") (pinfunction "DAC_#6") (pintype "bidirectional"))
      (node (ref "U03M") (pin "6") (pinfunction "DAC_6") (pintype "bidirectional"))
      (node (ref "U03M") (pin "@6") (pinfunction "DAC_@6") (pintype "bidirectional"))
    )
    (net (code "12") (name "BM_SYSOFF") (class "Default")
      (node (ref "R07B") (pin "2") (pinfunction "2_2") (pintype "passive"))
      (node (ref "U01B") (pin "15") (pinfunction "SYSOFF_15") (pintype "bidirectional"))
    )
    (net (code "13") (name "CE2") (class "Default")
      (node (ref "J02S") (pin "10") (pinfunction "CE2_10") (pintype "bidirectional"))
      (node (ref "R03D") (pin "2") (pinfunction "2_2") (pintype "passive"))
    )
    (net (code "14") (name "CL") (class "Default")
      (node (ref "J02S") (pin "5") (pinfunction "CL_5") (pintype "bidirectional"))
      (node (ref "U02M") (pin "9") (pinfunction "GP0_9") (pintype "bidirectional"))
    )
    (net (code "15") (name "D0") (class "Default")
      (node (ref "J02S") (pin "12") (pinfunction "D0_12") (pintype "bidirectional"))
      (node (ref "U01M") (pin "9") (pinfunction "GP0_9") (pintype "bidirectional"))
    )
    (net (code "16") (name "D1") (class "Default")
      (node (ref "J02S") (pin "13") (pinfunction "D1_13") (pintype "bidirectional"))
      (node (ref "U01M") (pin "10") (pinfunction "GP1_10") (pintype "bidirectional"))
    )
    (net (code "17") (name "D2") (class "Default")
      (node (ref "J02S") (pin "14") (pinfunction "D2_14") (pintype "bidirectional"))
      (node (ref "U01M") (pin "11") (pinfunction "GP2_11") (pintype "bidirectional"))
    )
    (net (code "18") (name "D3") (class "Default")
      (node (ref "J02S") (pin "15") (pinfunction "D3_15") (pintype "bidirectional"))
      (node (ref "U01M") (pin "12") (pinfunction "GP3_12") (pintype "bidirectional"))
    )
    (net (code "19") (name "D4") (class "Default")
      (node (ref "J02S") (pin "16") (pinfunction "D4_16") (pintype "bidirectional"))
      (node (ref "U01M") (pin "13") (pinfunction "GP4_13") (pintype "bidirectional"))
    )
    (net (code "20") (name "D5") (class "Default")
      (node (ref "J02S") (pin "17") (pinfunction "D5_17") (pintype "bidirectional"))
      (node (ref "U01M") (pin "14") (pinfunction "GP5_14") (pintype "bidirectional"))
    )
    (net (code "21") (name "D6") (class "Default")
      (node (ref "J02S") (pin "18") (pinfunction "D6_18") (pintype "bidirectional"))
      (node (ref "U01M") (pin "15") (pinfunction "GP6_15") (pintype "bidirectional"))
    )
    (net (code "22") (name "D7") (class "Default")
      (node (ref "J02S") (pin "19") (pinfunction "D7_19") (pintype "bidirectional"))
      (node (ref "U01M") (pin "16") (pinfunction "GP7_16") (pintype "bidirectional"))
    )
    (net (code "23") (name "E_INK_VDD") (class "Default")
      (node (ref "J02S") (pin "4") (pinfunction "VDD_4") (pintype "bidirectional"))
      (node (ref "R01D") (pin "1") (pinfunction "1_1") (pintype "passive"))
      (node (ref "R04M") (pin "2") (pinfunction "2_2") (pintype "passive"))
      (node (ref "R05D") (pin "1") (pinfunction "1_1") (pintype "passive"))
      (node (ref "R08D") (pin "1") (pinfunction "1_1") (pintype "passive"))
      (node (ref "R09D") (pin "1") (pinfunction "1_1") (pintype "passive"))
      (node (ref "SJ1") (pin "3") (pinfunction "3_3") (pintype "passive"))
      (node (ref "U03M") (pin "#11") (pinfunction "A1_#11") (pintype "bidirectional"))
      (node (ref "U03M") (pin "11") (pinfunction "A1_11") (pintype "bidirectional"))
      (node (ref "U03M") (pin "@11") (pinfunction "A1_@11") (pintype "bidirectional"))
    )
    (net (code "24") (name "FB2") (class "Default")
      (node (ref "C10B") (pin "1") (pinfunction "1_1") (pintype "passive"))
      (node (ref "R15B") (pin "1") (pinfunction "1_1") (pintype "passive"))
      (node (ref "R16B") (pin "2") (pinfunction "2_2") (pintype "passive"))
      (node (ref "U03B") (pin "5") (pinfunction "FB2_5") (pintype "bidirectional"))
    )
    (net (code "25") (name "GMODE2") (class "Default")
      (node (ref "J02S") (pin "27") (pinfunction "GMODE2_27") (pintype "bidirectional"))
      (node (ref "R04D") (pin "1") (pinfunction "1_1") (pintype "passive"))
      (node (ref "U03M") (pin "#15") (pinfunction "D2_#15") (pintype "bidirectional"))
      (node (ref "U03M") (pin "15") (pinfunction "D2_15") (pintype "bidirectional"))
      (node (ref "U03M") (pin "@15") (pinfunction "D2_@15") (pintype "bidirectional"))
    )
    (net (code "26") (name "GND") (class "Default")
      (node (ref "C01B") (pin "1") (pinfunction "1_1") (pintype "passive"))
      (node (ref "C01M") (pin "2") (pinfunction "2_2") (pintype "passive"))
      (node (ref "C01S") (pin "2") (pinfunction "2_2") (pintype "passive"))
      (node (ref "C02B") (pin "1") (pinfunction "1_1") (pintype "passive"))
      (node (ref "C02M") (pin "2") (pinfunction "2_2") (pintype "passive"))
      (node (ref "C02S") (pin "2") (pinfunction "2_2") (pintype "passive"))
      (node (ref "C03B") (pin "1") (pinfunction "1_1") (pintype "passive"))
      (node (ref "C03S") (pin "2") (pinfunction "2_2") (pintype "passive"))
      (node (ref "C04B") (pin "1") (pinfunction "1_1") (pintype "passive"))
      (node (ref "C04S") (pin "2") (pinfunction "2_2") (pintype "passive"))
      (node (ref "C05B") (pin "1") (pinfunction "1_1") (pintype "passive"))
      (node (ref "C06B") (pin "1") (pinfunction "1_1") (pintype "passive"))
      (node (ref "C09B") (pin "1") (pinfunction "1_1") (pintype "passive"))
      (node (ref "C11B") (pin "1") (pinfunction "1_1") (pintype "passive"))
      (node (ref "C12B") (pin "1") (pinfunction "1_1") (pintype "passive"))
      (node (ref "C13B") (pin "1") (pinfunction "1_1") (pintype "passive"))
      (node (ref "C14B") (pin "1") (pinfunction "1_1") (pintype "passive"))
      (node (ref "C15B") (pin "1") (pinfunction "1_1") (pintype "passive"))
      (node (ref "C16B") (pin "1") (pinfunction "1_1") (pintype "passive"))
      (node (ref "C17B") (pin "1") (pinfunction "1_1") (pintype "passive"))
      (node (ref "C19B") (pin "1") (pinfunction "1_1") (pintype "passive"))
      (node (ref "C20B") (pin "1") (pinfunction "1_1") (pintype "passive"))
      (node (ref "D03B") (pin "C") (pinfunction "C_C") (pintype "passive"))
      (node (ref "J01M") (pin "1") (pinfunction "1_1") (pintype "passive"))
      (node (ref "J01S") (pin "6") (pinfunction "VSS_6") (pintype "power_in"))
      (node (ref "J01S") (pin "MT1") (pinfunction "GND_MT1") (pintype "power_in"))
      (node (ref "J01S") (pin "MT2") (pinfunction "GND1_MT2") (pintype "power_in"))
      (node (ref "J02M") (pin "2") (pinfunction "2_2") (pintype "bidirectional"))
      (node (ref "J02S") (pin "3") (pinfunction "VSS_3") (pintype "bidirectional"))
      (node (ref "J03B") (pin "1") (pinfunction "-_1") (pintype "bidirectional"))
      (node (ref "J03M") (pin "2") (pinfunction "-_2") (pintype "power_in"))
      (node (ref "J07B") (pin "GND") (pinfunction "GND_GND") (pintype "bidirectional"))
      (node (ref "J07B") (pin "MT1") (pinfunction "GND_MT1") (pintype "bidirectional"))
      (node (ref "J07B") (pin "MT2") (pinfunction "GND_MT2") (pintype "bidirectional"))
      (node (ref "R01M") (pin "2") (pinfunction "2_2") (pintype "passive"))
      (node (ref "R02D") (pin "2") (pinfunction "2_2") (pintype "passive"))
      (node (ref "R02M") (pin "2") (pinfunction "2_2") (pintype "passive"))
      (node (ref "R03B") (pin "2") (pinfunction "2_2") (pintype "passive"))
      (node (ref "R03M") (pin "2") (pinfunction "2_2") (pintype "passive"))
      (node (ref "R05B") (pin "1") (pinfunction "1_1") (pintype "passive"))
      (node (ref "R05M") (pin "2") (pinfunction "2_2") (pintype "passive"))
      (node (ref "R06B") (pin "1") (pinfunction "1_1") (pintype "passive"))
      (node (ref "R06D") (pin "1") (pinfunction "1_1") (pintype "passive"))
      (node (ref "R06M") (pin "2") (pinfunction "2_2") (pintype "passive"))
      (node (ref "R07B") (pin "1") (pinfunction "1_1") (pintype "passive"))
      (node (ref "R07D") (pin "2") (pinfunction "2_2") (pintype "passive"))
      (node (ref "R08B") (pin "1") (pinfunction "1_1") (pintype "passive"))
      (node (ref "R09B") (pin "1") (pinfunction "1_1") (pintype "passive"))
      (node (ref "R10B") (pin "1") (pinfunction "1_1") (pintype "passive"))
      (node (ref "R14B") (pin "1") (pinfunction "1_1") (pintype "passive"))
      (node (ref "R16B") (pin "1") (pinfunction "1_1") (pintype "passive"))
      (node (ref "R18B") (pin "1") (pinfunction "A_1") (pintype "passive"))
      (node (ref "R21B") (pin "1") (pinfunction "1_1") (pintype "passive"))
      (node (ref "SJ1") (pin "1") (pinfunction "1_1") (pintype "passive"))
      (node (ref "U01B") (pin "8") (pinfunction "VSS_8") (pintype "bidirectional"))
      (node (ref "U01M") (pin "17") (pinfunction "GND_17") (pintype "power_in"))
      (node (ref "U01S") (pin "12") (pinfunction "SDO_12") (pintype "bidirectional"))
      (node (ref "U01S") (pin "2") (pinfunction "GND_2") (pintype "bidirectional"))
      (node (ref "U01S") (pin "4") (pinfunction "GND_4") (pintype "bidirectional"))
      (node (ref "U01S") (pin "5") (pinfunction "GND_5") (pintype "bidirectional"))
      (node (ref "U02B") (pin "2") (pinfunction "GND_2") (pintype "bidirectional"))
      (node (ref "U02M") (pin "17") (pinfunction "GND_17") (pintype "power_in"))
      (node (ref "U03B") (pin "3") (pinfunction "GND_3") (pintype "bidirectional"))
      (node (ref "U03B") (pin "7") (pinfunction "PGND_7") (pintype "bidirectional"))
      (node (ref "U03B") (pin "9") (pinfunction "PGND_9") (pintype "bidirectional"))
      (node (ref "U03M") (pin "#2") (pinfunction "GND_#2") (pintype "power_in"))
      (node (ref "U03M") (pin "#21") (pinfunction "GND_#21") (pintype "power_in"))
      (node (ref "U03M") (pin "2") (pinfunction "GND_2") (pintype "power_in"))
      (node (ref "U03M") (pin "21") (pinfunction "GND_21") (pintype "power_in"))
      (node (ref "U03M") (pin "@2") (pinfunction "GND_@2") (pintype "power_in"))
      (node (ref "U03M") (pin "@21") (pinfunction "GND_@21") (pintype "power_in"))
      (node (ref "U04B") (pin "5") (pinfunction "GND_5") (pintype "bidirectional"))
      (node (ref "U05B") (pin "2") (pinfunction "GND_2") (pintype "bidirectional"))
      (node (ref "U05B") (pin "3") (pinfunction "GND_3") (pintype "bidirectional"))
      (node (ref "U05B") (pin "6") (pinfunction "GND_6") (pintype "bidirectional"))
      (node (ref "U05B") (pin "7") (pinfunction "GND_7") (pintype "bidirectional"))
      (node (ref "U1") (pin "2") (pinfunction "VSS_2") (pintype "power_in"))
    )
    (net (code "27") (name "JTAG_TCK") (class "Default")
      (node (ref "J02M") (pin "3") (pinfunction "3_3") (pintype "bidirectional"))
      (node (ref "U03M") (pin "#19") (pinfunction "D6_#19") (pintype "bidirectional"))
      (node (ref "U03M") (pin "19") (pinfunction "D6_19") (pintype "bidirectional"))
      (node (ref "U03M") (pin "@19") (pinfunction "D6_@19") (pintype "bidirectional"))
    )
    (net (code "28") (name "JTAG_TMS") (class "Default")
      (node (ref "J02M") (pin "1") (pinfunction "1_1") (pintype "bidirectional"))
      (node (ref "U03M") (pin "#20") (pinfunction "D7_#20") (pintype "bidirectional"))
      (node (ref "U03M") (pin "20") (pinfunction "D7_20") (pintype "bidirectional"))
      (node (ref "U03M") (pin "@20") (pinfunction "D7_@20") (pintype "bidirectional"))
    )
    (net (code "29") (name "JTAG_TRST") (class "Default")
      (node (ref "J02M") (pin "5") (pinfunction "5_5") (pintype "bidirectional"))
      (node (ref "R02S") (pin "1") (pinfunction "1_1") (pintype "passive"))
      (node (ref "U03M") (pin "#16") (pinfunction "D3_#16") (pintype "bidirectional"))
      (node (ref "U03M") (pin "16") (pinfunction "D3_16") (pintype "bidirectional"))
      (node (ref "U03M") (pin "@16") (pinfunction "D3_@16") (pintype "bidirectional"))
    )
    (net (code "30") (name "LE") (class "Default")
      (node (ref "J02S") (pin "6") (pinfunction "LE_6") (pintype "bidirectional"))
      (node (ref "U02M") (pin "10") (pinfunction "GP1_10") (pintype "bidirectional"))
    )
    (net (code "31") (name "MCU_RST") (class "Default")
      (node (ref "J02M") (pin "4") (pinfunction "4_4") (pintype "bidirectional"))
      (node (ref "U03M") (pin "#23") (pinfunction "~{RST}_#23") (pintype "bidirectional"))
      (node (ref "U03M") (pin "23") (pinfunction "~{RST}_23") (pintype "bidirectional"))
      (node (ref "U03M") (pin "@23") (pinfunction "~{RST}_@23") (pintype "bidirectional"))
    )
    (net (code "32") (name "MCU_RX") (class "Default")
      (node (ref "J01M") (pin "4") (pinfunction "4_4") (pintype "passive"))
      (node (ref "U03M") (pin "#4") (pinfunction "RX_#4") (pintype "bidirectional"))
      (node (ref "U03M") (pin "4") (pinfunction "RX_4") (pintype "bidirectional"))
      (node (ref "U03M") (pin "@4") (pinfunction "RX_@4") (pintype "bidirectional"))
    )
    (net (code "33") (name "MCU_TX") (class "Default")
      (node (ref "J01M") (pin "5") (pinfunction "5_5") (pintype "passive"))
      (node (ref "U03M") (pin "#3") (pinfunction "TX_#3") (pintype "bidirectional"))
      (node (ref "U03M") (pin "3") (pinfunction "TX_3") (pintype "bidirectional"))
      (node (ref "U03M") (pin "@3") (pinfunction "TX_@3") (pintype "bidirectional"))
    )
    (net (code "34") (name "MCU_USB_DM") (class "Default")
      (node (ref "J07B") (pin "D-") (pinfunction "D-_D-") (pintype "bidirectional"))
    )
    (net (code "35") (name "MCU_USB_DP") (class "Default")
      (node (ref "J07B") (pin "D+") (pinfunction "D+_D+") (pintype "bidirectional"))
    )
    (net (code "36") (name "MCU_VBAT") (class "Default")
      (node (ref "J03M") (pin "1") (pinfunction "+_1") (pintype "power_in"))
      (node (ref "U03M") (pin "#22") (pinfunction "VBAT_#22") (pintype "power_in"))
      (node (ref "U03M") (pin "22") (pinfunction "VBAT_22") (pintype "power_in"))
      (node (ref "U03M") (pin "@22") (pinfunction "VBAT_@22") (pintype "power_in"))
    )
    (net (code "37") (name "MCU_VIN") (class "Default")
      (node (ref "U03M") (pin "#1") (pinfunction "VIN_#1") (pintype "power_in"))
      (node (ref "U03M") (pin "1") (pinfunction "VIN_1") (pintype "power_in"))
      (node (ref "U03M") (pin "@1") (pinfunction "VIN_@1") (pintype "power_in"))
    )
    (net (code "38") (name "MCU_WKP") (class "Default")
      (node (ref "SW01M") (pin "3") (pinfunction "2_3") (pintype "passive"))
      (node (ref "U03M") (pin "#5") (pinfunction "WKP_#5") (pintype "bidirectional"))
      (node (ref "U03M") (pin "5") (pinfunction "WKP_5") (pintype "bidirectional"))
      (node (ref "U03M") (pin "@5") (pinfunction "WKP_@5") (pintype "bidirectional"))
    )
    (net (code "39") (name "N$31") (class "Default")
      (node (ref "U02M") (pin "14") (pinfunction "GP5_14") (pintype "bidirectional"))
    )
    (net (code "40") (name "NEG_EN") (class "Default")
      (node (ref "U02M") (pin "13") (pinfunction "GP4_13") (pintype "bidirectional"))
      (node (ref "U03B") (pin "2") (pinfunction "~{SHDN1}_2") (pintype "bidirectional"))
    )
    (net (code "41") (name "NFB1") (class "Default")
      (node (ref "C08B") (pin "1") (pinfunction "1_1") (pintype "passive"))
      (node (ref "R13B") (pin "1") (pinfunction "1_1") (pintype "passive"))
      (node (ref "R14B") (pin "2") (pinfunction "2_2") (pintype "passive"))
      (node (ref "U03B") (pin "1") (pinfunction "NFB1_1") (pintype "bidirectional"))
    )
    (net (code "42") (name "Net-(C02B-Pad2)") (class "Default")
      (node (ref "C02B") (pin "2") (pinfunction "2_2") (pintype "passive"))
      (node (ref "J04B") (pin "2") (pinfunction "2_2") (pintype "passive"))
      (node (ref "J05B") (pin "1") (pinfunction "1_1") (pintype "passive"))
      (node (ref "U01B") (pin "2") (pinfunction "BAT_2") (pintype "bidirectional"))
      (node (ref "U01B") (pin "3") (pinfunction "BAT_3") (pintype "bidirectional"))
    )
    (net (code "43") (name "Net-(C07B-Pad2)") (class "Default")
      (node (ref "C07B") (pin "2") (pinfunction "2_2") (pintype "passive"))
      (node (ref "D03B") (pin "A") (pinfunction "A_A") (pintype "passive"))
      (node (ref "D04B") (pin "C") (pinfunction "C_C") (pintype "passive"))
    )
    (net (code "44") (name "Net-(D01B-PadA)") (class "Default")
      (node (ref "D01B") (pin "A") (pinfunction "A_A") (pintype "passive"))
      (node (ref "R01B") (pin "2") (pinfunction "2_2") (pintype "passive"))
    )
    (net (code "45") (name "Net-(D01S-PadA)") (class "Default")
      (node (ref "D01S") (pin "A") (pinfunction "A_A") (pintype "passive"))
      (node (ref "R01S") (pin "1") (pinfunction "1_1") (pintype "passive"))
    )
    (net (code "46") (name "Net-(D02B-PadA)") (class "Default")
      (node (ref "D02B") (pin "A") (pinfunction "A_A") (pintype "passive"))
      (node (ref "R02B") (pin "1") (pinfunction "1_1") (pintype "passive"))
    )
    (net (code "47") (name "Net-(D06B-PadA)") (class "Default")
      (node (ref "D06B") (pin "A") (pinfunction "A_A") (pintype "passive"))
      (node (ref "R20B") (pin "2") (pinfunction "2_2") (pintype "passive"))
    )
    (net (code "48") (name "Net-(J02S-CE1)") (class "Default")
      (node (ref "J02S") (pin "9") (pinfunction "CE1_9") (pintype "bidirectional"))
      (node (ref "R02D") (pin "1") (pinfunction "1_1") (pintype "passive"))
    )
    (net (code "49") (name "Net-(J02S-GMODE1)") (class "Default")
      (node (ref "J02S") (pin "28") (pinfunction "GMODE1_28") (pintype "bidirectional"))
      (node (ref "R04D") (pin "2") (pinfunction "2_2") (pintype "passive"))
    )
    (net (code "50") (name "Net-(J02S-RL)") (class "Default")
      (node (ref "J02S") (pin "29") (pinfunction "RL_29") (pintype "bidirectional"))
      (node (ref "SJ1") (pin "2") (pinfunction "2_2") (pintype "passive"))
    )
    (net (code "51") (name "Net-(J02S-U1CE1)") (class "Default")
      (node (ref "J02S") (pin "31") (pinfunction "U1CE1_31") (pintype "bidirectional"))
      (node (ref "R06D") (pin "2") (pinfunction "2_2") (pintype "passive"))
    )
    (net (code "52") (name "Net-(J02S-U1CE2)") (class "Default")
      (node (ref "J02S") (pin "30") (pinfunction "U1CE2_30") (pintype "bidirectional"))
      (node (ref "R05D") (pin "2") (pinfunction "2_2") (pintype "passive"))
    )
    (net (code "53") (name "Net-(J02S-U2CE1)") (class "Default")
      (node (ref "J02S") (pin "36") (pinfunction "U2CE1_36") (pintype "bidirectional"))
      (node (ref "R09D") (pin "2") (pinfunction "2_2") (pintype "passive"))
    )
    (net (code "54") (name "Net-(J02S-U2CE2)") (class "Default")
      (node (ref "J02S") (pin "35") (pinfunction "U2CE2_35") (pintype "bidirectional"))
      (node (ref "R08D") (pin "2") (pinfunction "2_2") (pintype "passive"))
    )
    (net (code "55") (name "Net-(J02S-U2CKV)") (class "Default")
      (node (ref "J02S") (pin "38") (pinfunction "U2CKV_38") (pintype "bidirectional"))
      (node (ref "R10D") (pin "1") (pinfunction "1_1") (pintype "passive"))
    )
    (net (code "56") (name "Net-(J02S-U2SPV)") (class "Default")
      (node (ref "J02S") (pin "37") (pinfunction "U2SPV_37") (pintype "bidirectional"))
      (node (ref "R11D") (pin "1") (pinfunction "1_1") (pintype "passive"))
    )
    (net (code "57") (name "Net-(J02S-VBORDER)") (class "Default")
      (node (ref "J02S") (pin "34") (pinfunction "VBORDER_34") (pintype "bidirectional"))
      (node (ref "R07D") (pin "1") (pinfunction "1_1") (pintype "passive"))
    )
    (net (code "58") (name "Net-(R18B-E)") (class "Default")
      (node (ref "R17B") (pin "1") (pinfunction "1_1") (pintype "passive"))
      (node (ref "R18B") (pin "3") (pinfunction "E_3") (pintype "passive"))
    )
    (net (code "59") (name "Net-(R18B-S)") (class "Default")
      (node (ref "R18B") (pin "2") (pinfunction "S_2") (pintype "passive"))
      (node (ref "U06B") (pin "5") (pinfunction "+IN2_5") (pintype "input"))
    )
    (net (code "60") (name "Net-(TP01B-TP)") (class "Default")
      (node (ref "R11B") (pin "1") (pinfunction "1_1") (pintype "passive"))
      (node (ref "TP01B") (pin "P$1") (pinfunction "TP_P$1") (pintype "bidirectional"))
      (node (ref "U02B") (pin "1") (pinfunction "EN_1") (pintype "bidirectional"))
    )
    (net (code "61") (name "Net-(U$1-TP)") (class "Default")
      (node (ref "U$1") (pin "P$1") (pinfunction "TP_P$1") (pintype "bidirectional"))
      (node (ref "U01M") (pin "4") (pinfunction "/RST_4") (pintype "input"))
    )
    (net (code "62") (name "Net-(U$2-TP)") (class "Default")
      (node (ref "U$2") (pin "P$1") (pinfunction "TP_P$1") (pintype "bidirectional"))
      (node (ref "U01M") (pin "7") (pinfunction "INT_7") (pintype "output"))
    )
    (net (code "63") (name "Net-(U$3-TP)") (class "Default")
      (node (ref "U$3") (pin "P$1") (pinfunction "TP_P$1") (pintype "bidirectional"))
      (node (ref "U02M") (pin "4") (pinfunction "/RST_4") (pintype "input"))
    )
    (net (code "64") (name "Net-(U$4-TP)") (class "Default")
      (node (ref "U$4") (pin "P$1") (pinfunction "TP_P$1") (pintype "bidirectional"))
      (node (ref "U02M") (pin "7") (pinfunction "INT_7") (pintype "output"))
    )
    (net (code "65") (name "Net-(U1-PROG)") (class "Default")
      (node (ref "R21B") (pin "2") (pinfunction "2_2") (pintype "passive"))
      (node (ref "U1") (pin "5") (pinfunction "PROG_5") (pintype "input"))
    )
    (net (code "66") (name "Net-(U1-STAT)") (class "Default")
      (node (ref "D06B") (pin "C") (pinfunction "C_C") (pintype "passive"))
      (node (ref "U1") (pin "1") (pinfunction "STAT_1") (pintype "output"))
    )
    (net (code "67") (name "Net-(U01B-EN1)") (class "Default")
      (node (ref "R03B") (pin "1") (pinfunction "1_1") (pintype "passive"))
      (node (ref "U01B") (pin "6") (pinfunction "EN1_6") (pintype "bidirectional"))
    )
    (net (code "68") (name "Net-(U01B-EN2)") (class "Default")
      (node (ref "R04B") (pin "1") (pinfunction "1_1") (pintype "passive"))
      (node (ref "U01B") (pin "5") (pinfunction "EN2_5") (pintype "bidirectional"))
    )
    (net (code "69") (name "Net-(U01B-ILIM)") (class "Default")
      (node (ref "R08B") (pin "2") (pinfunction "2_2") (pintype "passive"))
      (node (ref "U01B") (pin "12") (pinfunction "ILIM_12") (pintype "bidirectional"))
    )
    (net (code "70") (name "Net-(U01B-ISET)") (class "Default")
      (node (ref "R09B") (pin "2") (pinfunction "2_2") (pintype "passive"))
      (node (ref "U01B") (pin "16") (pinfunction "ISET_16") (pintype "bidirectional"))
    )
    (net (code "71") (name "Net-(U01B-TMR)") (class "Default")
      (node (ref "R06B") (pin "2") (pinfunction "2_2") (pintype "passive"))
      (node (ref "U01B") (pin "14") (pinfunction "TMR_14") (pintype "bidirectional"))
    )
    (net (code "72") (name "Net-(U01B-TS)") (class "Default")
      (node (ref "R10B") (pin "2") (pinfunction "2_2") (pintype "passive"))
      (node (ref "U01B") (pin "1") (pinfunction "TS_1") (pintype "bidirectional"))
    )
    (net (code "73") (name "Net-(U01M-A0)") (class "Default")
      (node (ref "R01M") (pin "1") (pinfunction "1_1") (pintype "passive"))
      (node (ref "U01M") (pin "3") (pinfunction "A0_3") (pintype "input"))
    )
    (net (code "74") (name "Net-(U01M-A1)") (class "Default")
      (node (ref "R02M") (pin "1") (pinfunction "1_1") (pintype "passive"))
      (node (ref "U01M") (pin "2") (pinfunction "A1_2") (pintype "input"))
    )
    (net (code "75") (name "Net-(U01M-A2)") (class "Default")
      (node (ref "R03M") (pin "1") (pinfunction "1_1") (pintype "passive"))
      (node (ref "U01M") (pin "1") (pinfunction "A2_1") (pintype "input"))
    )
    (net (code "76") (name "Net-(U01S-CS)") (class "Default")
      (node (ref "C02S") (pin "1") (pinfunction "1_1") (pintype "passive"))
      (node (ref "C03S") (pin "1") (pinfunction "1_1") (pintype "passive"))
      (node (ref "C04S") (pin "1") (pinfunction "1_1") (pintype "passive"))
      (node (ref "U01S") (pin "1") (pinfunction "VDD_1") (pintype "bidirectional"))
      (node (ref "U01S") (pin "6") (pinfunction "VS_6") (pintype "bidirectional"))
      (node (ref "U01S") (pin "7") (pinfunction "CS_7") (pintype "bidirectional"))
    )
    (net (code "77") (name "Net-(U01S-INT1)") (class "Default")
      (node (ref "R02S") (pin "2") (pinfunction "2_2") (pintype "passive"))
      (node (ref "U01S") (pin "8") (pinfunction "INT1_8") (pintype "bidirectional"))
    )
    (net (code "78") (name "Net-(U02B-LX)") (class "Default")
      (node (ref "L01B") (pin "1") (pinfunction "1_1") (pintype "passive"))
      (node (ref "U02B") (pin "3") (pinfunction "LX_3") (pintype "bidirectional"))
    )
    (net (code "79") (name "Net-(U02M-A0)") (class "Default")
      (node (ref "R04M") (pin "1") (pinfunction "1_1") (pintype "passive"))
      (node (ref "U02M") (pin "3") (pinfunction "A0_3") (pintype "input"))
    )
    (net (code "80") (name "Net-(U02M-A1)") (class "Default")
      (node (ref "R05M") (pin "1") (pinfunction "1_1") (pintype "passive"))
      (node (ref "U02M") (pin "2") (pinfunction "A1_2") (pintype "input"))
    )
    (net (code "81") (name "Net-(U02M-A2)") (class "Default")
      (node (ref "R06M") (pin "1") (pinfunction "1_1") (pintype "passive"))
      (node (ref "U02M") (pin "1") (pinfunction "A2_1") (pintype "input"))
    )
    (net (code "82") (name "Net-(U03B-SW1)") (class "Default")
      (node (ref "C07B") (pin "1") (pinfunction "1_1") (pintype "passive"))
      (node (ref "L02B") (pin "P$2") (pinfunction "P$2_P$2") (pintype "bidirectional"))
      (node (ref "U03B") (pin "10") (pinfunction "SW1_10") (pintype "bidirectional"))
    )
    (net (code "83") (name "Net-(U03B-SW2)") (class "Default")
      (node (ref "D05B") (pin "A") (pinfunction "A_A") (pintype "passive"))
      (node (ref "L03B") (pin "P$2") (pinfunction "P$2_P$2") (pintype "bidirectional"))
      (node (ref "U03B") (pin "6") (pinfunction "SW2_6") (pintype "bidirectional"))
    )
    (net (code "84") (name "OE") (class "Default")
      (node (ref "J02S") (pin "7") (pinfunction "OE_7") (pintype "bidirectional"))
      (node (ref "U02M") (pin "11") (pinfunction "GP2_11") (pintype "bidirectional"))
    )
    (net (code "85") (name "POS_EN") (class "Default")
      (node (ref "U02M") (pin "16") (pinfunction "GP7_16") (pintype "bidirectional"))
      (node (ref "U03B") (pin "4") (pinfunction "~{SHDN2}_4") (pintype "bidirectional"))
    )
    (net (code "86") (name "SCL") (class "Default")
      (node (ref "R08M") (pin "2") (pinfunction "2_2") (pintype "passive"))
      (node (ref "U01M") (pin "19") (pinfunction "SCL_19") (pintype "bidirectional"))
      (node (ref "U01S") (pin "14") (pinfunction "SCL_14") (pintype "bidirectional"))
      (node (ref "U02M") (pin "19") (pinfunction "SCL_19") (pintype "bidirectional"))
      (node (ref "U03M") (pin "#14") (pinfunction "D1_#14") (pintype "bidirectional"))
      (node (ref "U03M") (pin "14") (pinfunction "D1_14") (pintype "bidirectional"))
      (node (ref "U03M") (pin "@14") (pinfunction "D1_@14") (pintype "bidirectional"))
    )
    (net (code "87") (name "SDA") (class "Default")
      (node (ref "R09M") (pin "2") (pinfunction "2_2") (pintype "passive"))
      (node (ref "U01M") (pin "20") (pinfunction "SDA_20") (pintype "bidirectional"))
      (node (ref "U01S") (pin "13") (pinfunction "SDA_13") (pintype "bidirectional"))
      (node (ref "U02M") (pin "20") (pinfunction "SDA_20") (pintype "bidirectional"))
      (node (ref "U03M") (pin "#13") (pinfunction "D0_#13") (pintype "bidirectional"))
      (node (ref "U03M") (pin "13") (pinfunction "D0_13") (pintype "bidirectional"))
      (node (ref "U03M") (pin "@13") (pinfunction "D0_@13") (pintype "bidirectional"))
    )
    (net (code "88") (name "SD_CD") (class "Default")
      (node (ref "J01S") (pin "CD1") (pinfunction "CARD_DETECT_CD1") (pintype "passive"))
      (node (ref "U$5") (pin "P$1") (pinfunction "TP_P$1") (pintype "bidirectional"))
    )
    (net (code "89") (name "SHR") (class "Default")
      (node (ref "J02S") (pin "8") (pinfunction "SHR_8") (pintype "bidirectional"))
      (node (ref "R01D") (pin "2") (pinfunction "2_2") (pintype "passive"))
      (node (ref "R03D") (pin "1") (pinfunction "1_1") (pintype "passive"))
    )
    (net (code "90") (name "SMPS_CTRL") (class "Default")
      (node (ref "Q01B") (pin "1") (pinfunction "G_1") (pintype "passive"))
      (node (ref "R12B") (pin "1") (pinfunction "1_1") (pintype "passive"))
      (node (ref "U02M") (pin "15") (pinfunction "GP6_15") (pintype "bidirectional"))
    )
    (net (code "91") (name "SPH") (class "Default")
      (node (ref "J02S") (pin "11") (pinfunction "SPH_11") (pintype "bidirectional"))
      (node (ref "U02M") (pin "12") (pinfunction "GP3_12") (pintype "bidirectional"))
    )
    (net (code "92") (name "SPI_CS") (class "Default")
      (node (ref "D01S") (pin "C") (pinfunction "C_C") (pintype "passive"))
      (node (ref "J01S") (pin "2") (pinfunction "CS_2") (pintype "input"))
      (node (ref "U03M") (pin "#10") (pinfunction "A2_#10") (pintype "bidirectional"))
      (node (ref "U03M") (pin "10") (pinfunction "A2_10") (pintype "bidirectional"))
      (node (ref "U03M") (pin "@10") (pinfunction "A2_@10") (pintype "bidirectional"))
    )
    (net (code "93") (name "SPI_MISO") (class "Default")
      (node (ref "J01S") (pin "7") (pinfunction "DATA_OUT_7") (pintype "output"))
      (node (ref "U03M") (pin "#8") (pinfunction "A4_#8") (pintype "bidirectional"))
      (node (ref "U03M") (pin "8") (pinfunction "A4_8") (pintype "bidirectional"))
      (node (ref "U03M") (pin "@8") (pinfunction "A4_@8") (pintype "bidirectional"))
    )
    (net (code "94") (name "SPI_MOSI") (class "Default")
      (node (ref "J01S") (pin "3") (pinfunction "DATA_IN_3") (pintype "input"))
      (node (ref "U03M") (pin "#7") (pinfunction "A5_#7") (pintype "bidirectional"))
      (node (ref "U03M") (pin "7") (pinfunction "A5_7") (pintype "bidirectional"))
      (node (ref "U03M") (pin "@7") (pinfunction "A5_@7") (pintype "bidirectional"))
    )
    (net (code "95") (name "SPI_SCK") (class "Default")
      (node (ref "J01S") (pin "5") (pinfunction "SCLK_5") (pintype "input"))
      (node (ref "R01S") (pin "2") (pinfunction "2_2") (pintype "passive"))
      (node (ref "U03M") (pin "#9") (pinfunction "A3_#9") (pintype "bidirectional"))
      (node (ref "U03M") (pin "9") (pinfunction "A3_9") (pintype "bidirectional"))
      (node (ref "U03M") (pin "@9") (pinfunction "A3_@9") (pintype "bidirectional"))
    )
    (net (code "96") (name "U1CKV") (class "Default")
      (node (ref "J02S") (pin "33") (pinfunction "U1CKV_33") (pintype "bidirectional"))
      (node (ref "R10D") (pin "2") (pinfunction "2_2") (pintype "passive"))
      (node (ref "U03M") (pin "#18") (pinfunction "D5_#18") (pintype "bidirectional"))
      (node (ref "U03M") (pin "18") (pinfunction "D5_18") (pintype "bidirectional"))
      (node (ref "U03M") (pin "@18") (pinfunction "D5_@18") (pintype "bidirectional"))
    )
    (net (code "97") (name "U1SPV") (class "Default")
      (node (ref "J02S") (pin "32") (pinfunction "U1SPV_32") (pintype "bidirectional"))
      (node (ref "R11D") (pin "2") (pinfunction "2_2") (pintype "passive"))
      (node (ref "U03M") (pin "#17") (pinfunction "D4_#17") (pintype "bidirectional"))
      (node (ref "U03M") (pin "17") (pinfunction "D4_17") (pintype "bidirectional"))
      (node (ref "U03M") (pin "@17") (pinfunction "D4_@17") (pintype "bidirectional"))
    )
    (net (code "98") (name "VBUS") (class "Default")
      (node (ref "C01B") (pin "2") (pinfunction "2_2") (pintype "passive"))
      (node (ref "C19B") (pin "2") (pinfunction "2_2") (pintype "passive"))
      (node (ref "J01B") (pin "1") (pinfunction "1_1") (pintype "passive"))
      (node (ref "J07B") (pin "VBUS") (pinfunction "VBUS_VBUS") (pintype "bidirectional"))
      (node (ref "R20B") (pin "1") (pinfunction "1_1") (pintype "passive"))
      (node (ref "U01B") (pin "13") (pinfunction "IN_13") (pintype "bidirectional"))
      (node (ref "U1") (pin "4") (pinfunction "VIN_4") (pintype "power_in"))
    )
    (net (code "99") (name "VCOM") (class "Default")
      (node (ref "C17B") (pin "2") (pinfunction "2_2") (pintype "passive"))
      (node (ref "J02S") (pin "22") (pinfunction "VCOM_22") (pintype "bidirectional"))
      (node (ref "J13B") (pin "1") (pinfunction "1_1") (pintype "passive"))
      (node (ref "U06B") (pin "6") (pinfunction "-IN2_6") (pintype "input"))
      (node (ref "U06B") (pin "7") (pinfunction "OUT2_7") (pintype "output"))
    )
    (net (code "100") (name "VIN") (class "Default")
      (node (ref "C09B") (pin "2") (pinfunction "2_2") (pintype "passive"))
      (node (ref "J08B") (pin "1") (pinfunction "1_1") (pintype "passive"))
      (node (ref "L02B") (pin "P$1") (pinfunction "P$1_P$1") (pintype "bidirectional"))
      (node (ref "L03B") (pin "P$1") (pinfunction "P$1_P$1") (pintype "bidirectional"))
      (node (ref "Q01B") (pin "3") (pinfunction "D_3") (pintype "passive"))
      (node (ref "U03B") (pin "8") (pinfunction "VIN_8") (pintype "bidirectional"))
    )
    (net (code "101") (name "unconnected-(J01M-Pad2)") (class "Default")
      (node (ref "J01M") (pin "2") (pinfunction "2_2") (pintype "passive"))
    )
    (net (code "102") (name "unconnected-(J01S-CARD_DETECT1-PadCD2)") (class "Default")
      (node (ref "J01S") (pin "CD2") (pinfunction "CARD_DETECT1_CD2") (pintype "passive"))
    )
    (net (code "103") (name "unconnected-(J01S-DAT1-Pad8)") (class "Default")
      (node (ref "J01S") (pin "8") (pinfunction "DAT1_8") (pintype "bidirectional"))
    )
    (net (code "104") (name "unconnected-(J01S-DAT2-Pad1)") (class "Default")
      (node (ref "J01S") (pin "1") (pinfunction "DAT2_1") (pintype "bidirectional"))
    )
    (net (code "105") (name "unconnected-(J02S-NC-20-Pad20)") (class "Default")
      (node (ref "J02S") (pin "20") (pinfunction "NC-20_20") (pintype "bidirectional"))
    )
    (net (code "106") (name "unconnected-(J02S-NC-21-Pad21)") (class "Default")
      (node (ref "J02S") (pin "21") (pinfunction "NC-21_21") (pintype "bidirectional"))
    )
    (net (code "107") (name "unconnected-(J02S-NC-25-Pad25)") (class "Default")
      (node (ref "J02S") (pin "25") (pinfunction "NC-25_25") (pintype "bidirectional"))
    )
    (net (code "108") (name "unconnected-(J02S-NC-26-Pad26)") (class "Default")
      (node (ref "J02S") (pin "26") (pinfunction "NC-26_26") (pintype "bidirectional"))
    )
    (net (code "109") (name "unconnected-(J02S-NC-39-Pad39)") (class "Default")
      (node (ref "J02S") (pin "39") (pinfunction "NC-39_39") (pintype "bidirectional"))
    )
    (net (code "110") (name "unconnected-(J03B-PAD1-PadNC1)") (class "Default")
      (node (ref "J03B") (pin "NC1") (pinfunction "PAD1_NC1") (pintype "bidirectional"))
    )
    (net (code "111") (name "unconnected-(J03B-PAD2-PadNC2)") (class "Default")
      (node (ref "J03B") (pin "NC2") (pinfunction "PAD2_NC2") (pintype "bidirectional"))
    )
    (net (code "112") (name "unconnected-(U01S-INT2-Pad9)") (class "Default")
      (node (ref "U01S") (pin "9") (pinfunction "INT2_9") (pintype "bidirectional"))
    )
    (net (code "113") (name "unconnected-(U01S-NC-Pad3)") (class "Default")
      (node (ref "U01S") (pin "3") (pinfunction "NC_3") (pintype "bidirectional"))
    )
    (net (code "114") (name "unconnected-(U01S-NC-Pad10)") (class "Default")
      (node (ref "U01S") (pin "10") (pinfunction "NC_10") (pintype "bidirectional"))
    )
    (net (code "115") (name "unconnected-(U01S-NC-Pad11)") (class "Default")
      (node (ref "U01S") (pin "11") (pinfunction "NC_11") (pintype "bidirectional"))
    )
    (net (code "116") (name "unconnected-(U04B-NC-Pad4)") (class "Default")
      (node (ref "U04B") (pin "4") (pinfunction "NC_4") (pintype "bidirectional"))
    )
    (net (code "117") (name "unconnected-(U04B-NC-Pad8)") (class "Default")
      (node (ref "U04B") (pin "8") (pinfunction "NC_8") (pintype "bidirectional"))
    )
    (net (code "118") (name "unconnected-(U05B-NC-Pad4)") (class "Default")
      (node (ref "U05B") (pin "4") (pinfunction "NC_4") (pintype "bidirectional"))
    )
    (net (code "119") (name "unconnected-(U05B-NC-Pad5)") (class "Default")
      (node (ref "U05B") (pin "5") (pinfunction "NC_5") (pintype "bidirectional"))
    )
    (net (code "120") (name "unconnected-(U06B-+IN1-Pad3)") (class "Default")
      (node (ref "U06B") (pin "3") (pinfunction "+IN1_3") (pintype "input"))
    )
    (net (code "121") (name "unconnected-(U06B--IN1-Pad2)") (class "Default")
      (node (ref "U06B") (pin "2") (pinfunction "-IN1_2") (pintype "input"))
    )
    (net (code "122") (name "unconnected-(U06B-OUT1-Pad1)") (class "Default")
      (node (ref "U06B") (pin "1") (pinfunction "OUT1_1") (pintype "output"))
    )
  )
)
